# 519_jetson_nano_020002.net
KiCad netlist of a schematic drawn in EAGLE
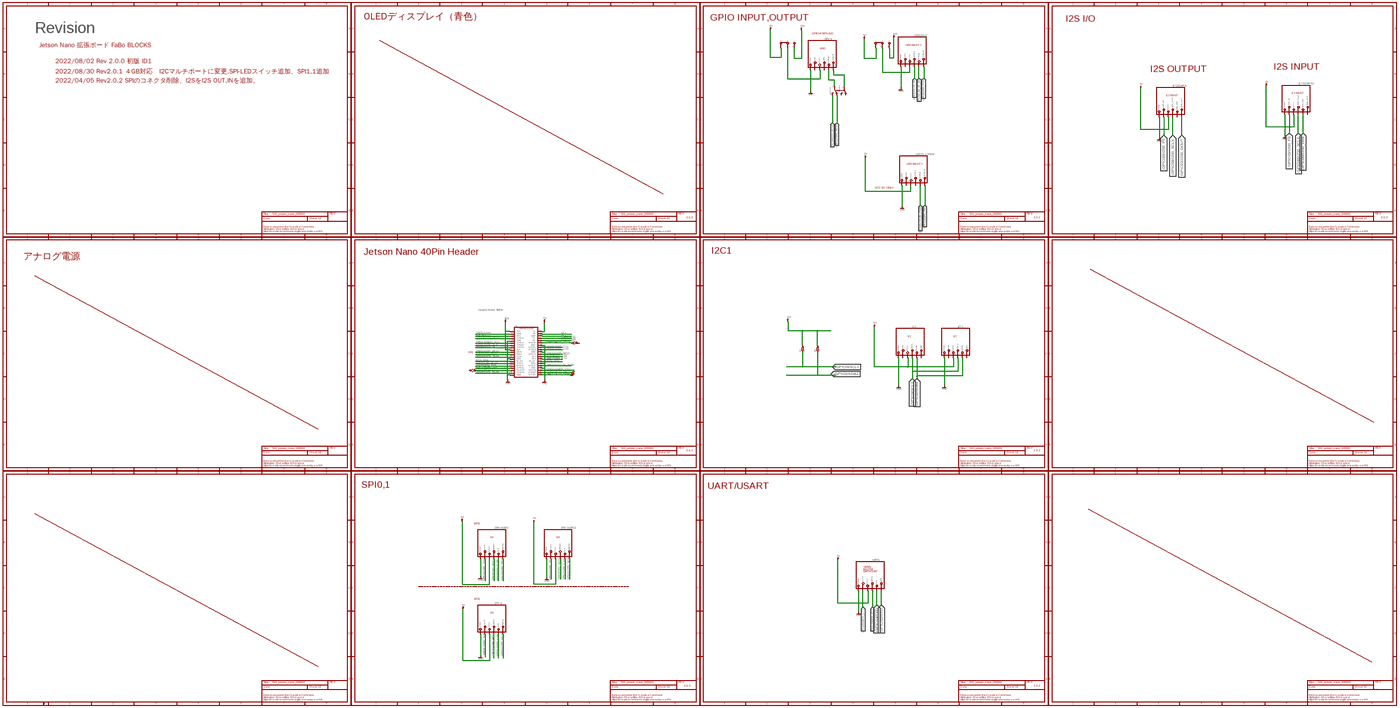
[diagram p0: schematic, sheet 1, overview]
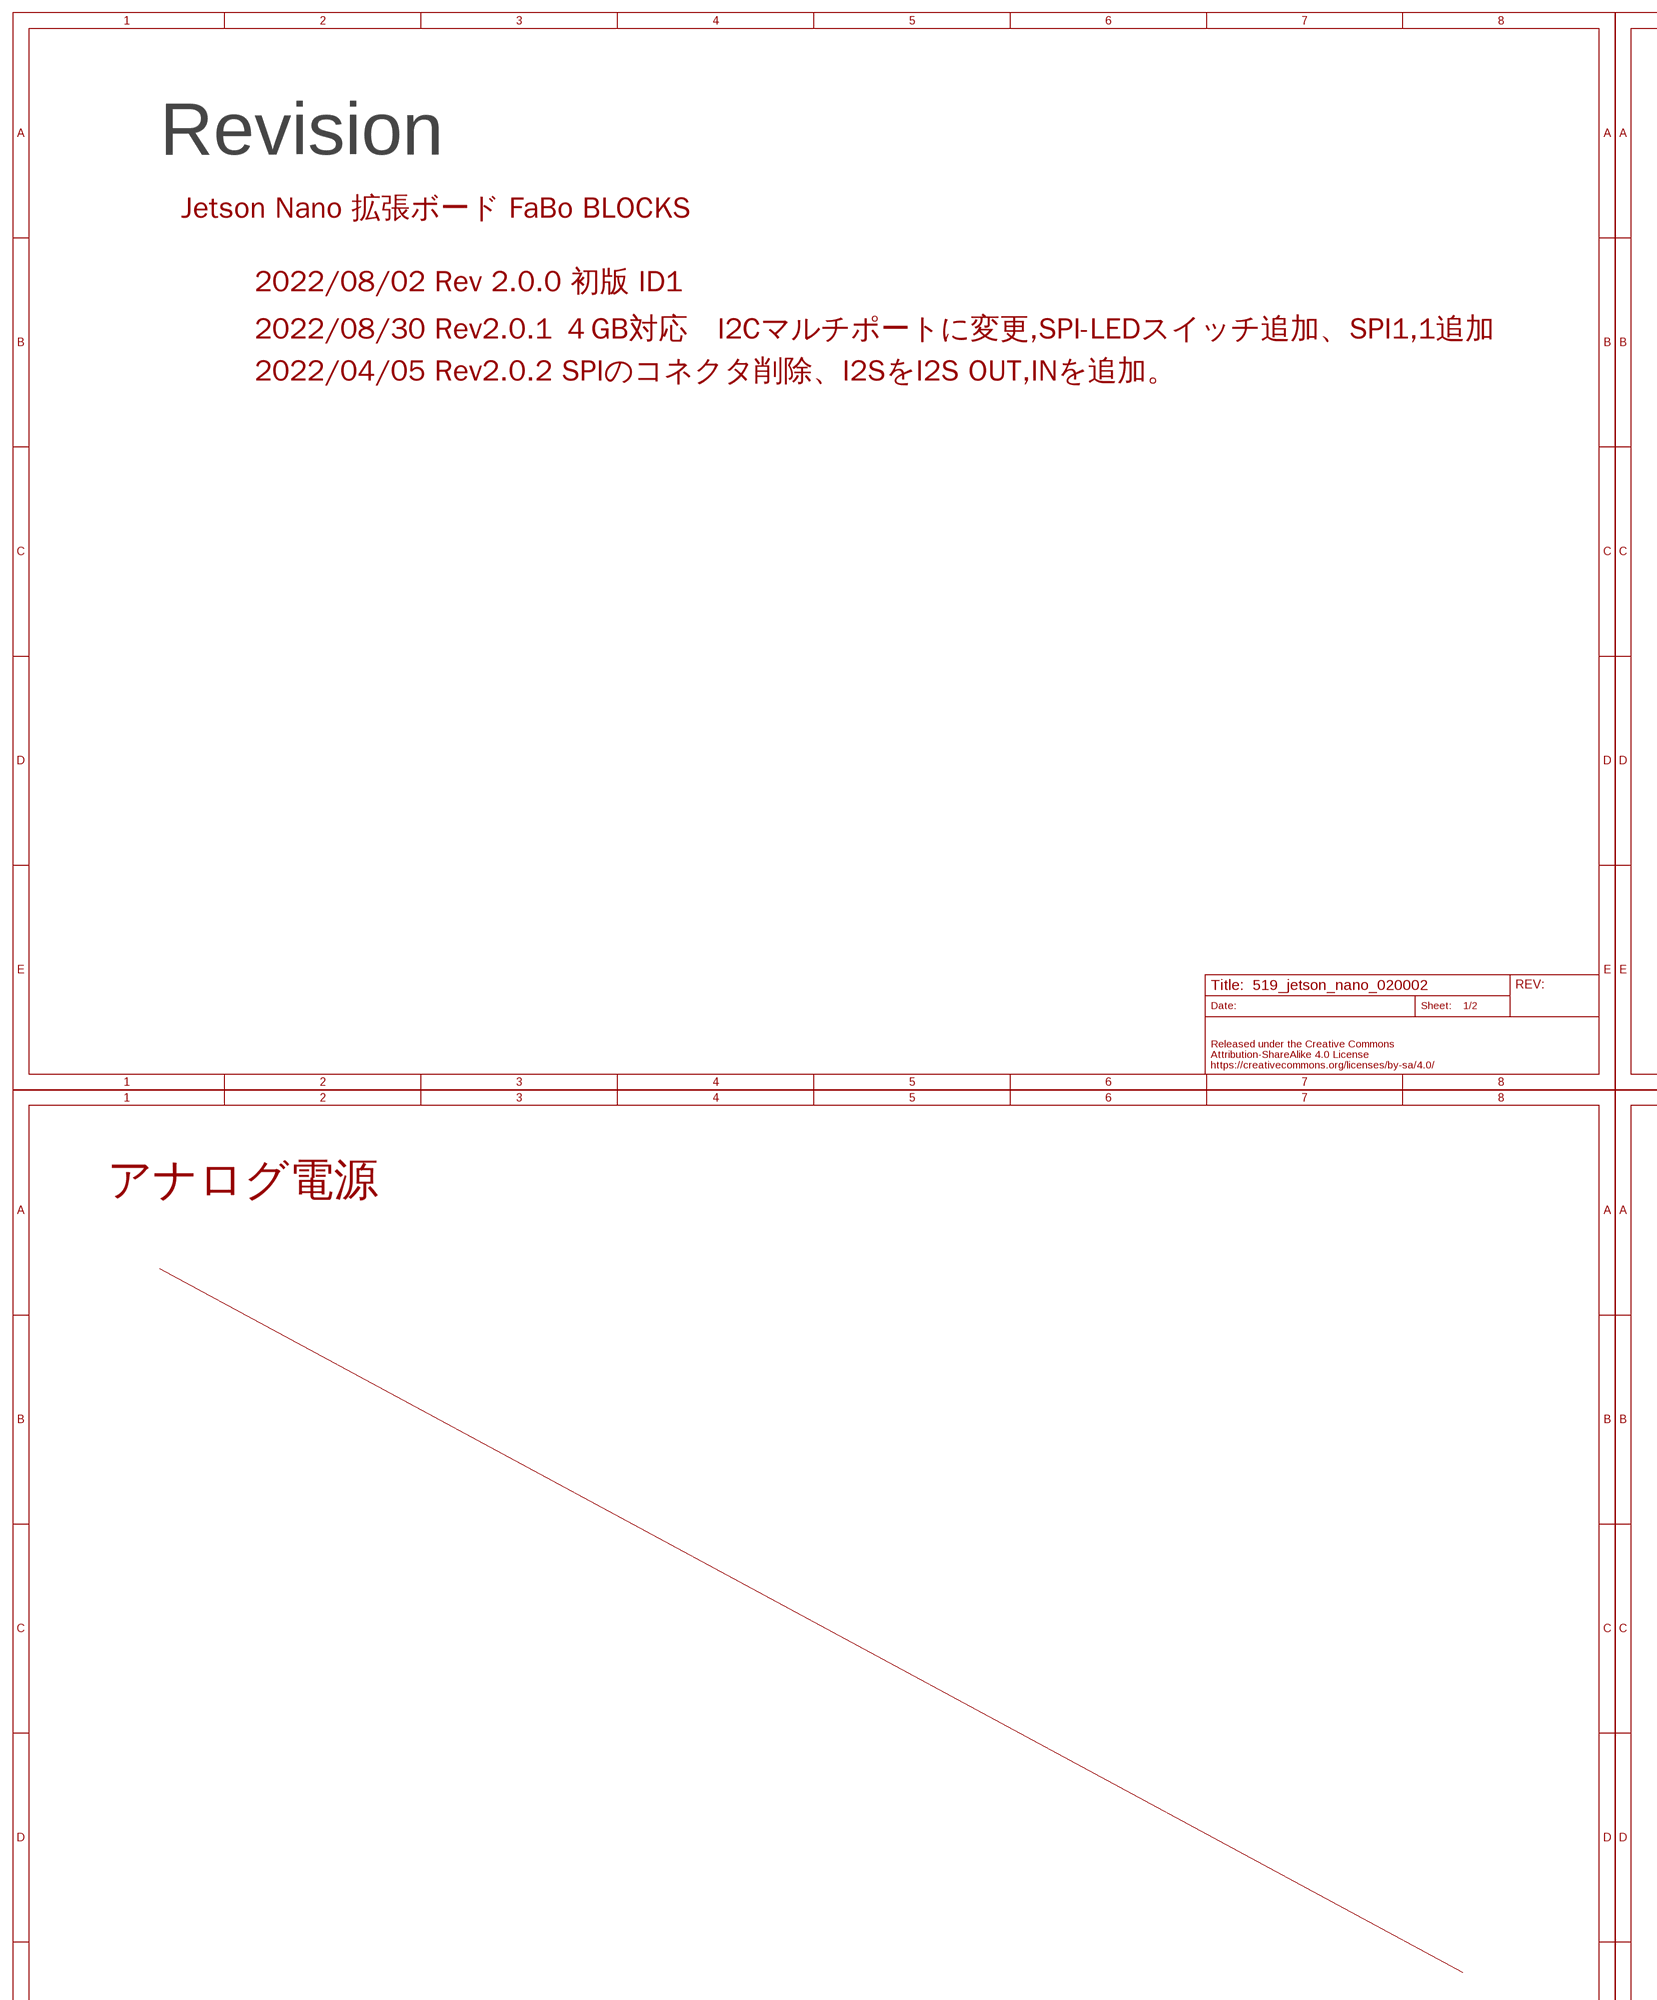
[diagram p1: schematic, sheet 1, part 1 of 8]
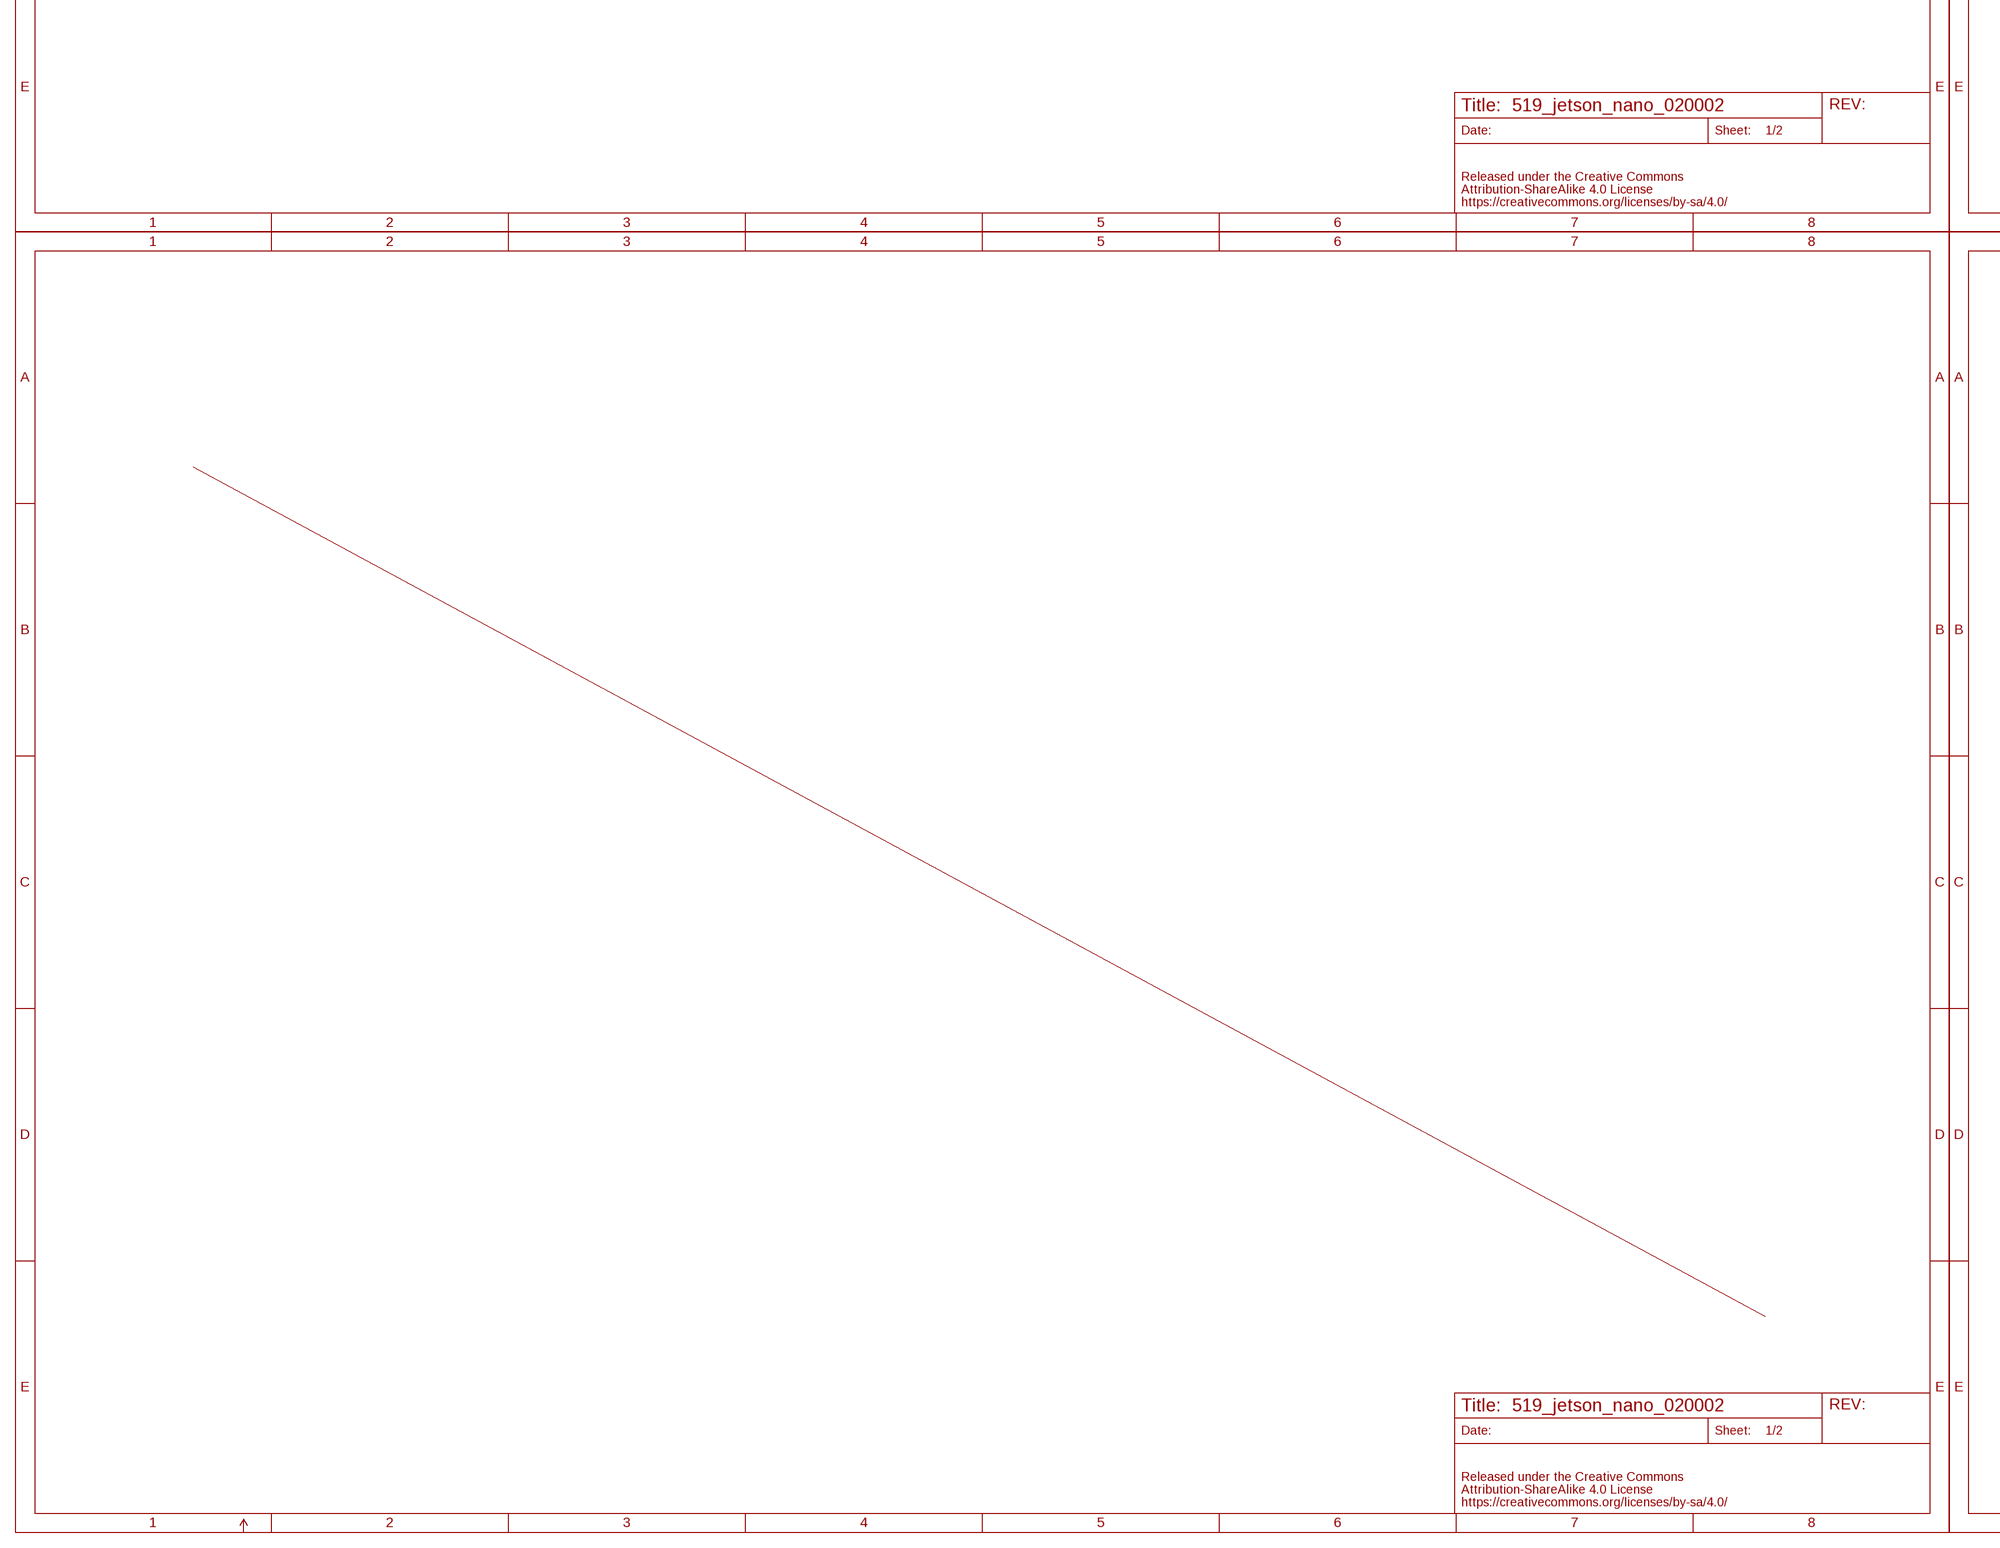
[diagram p2: schematic, sheet 1, part 2 of 8]
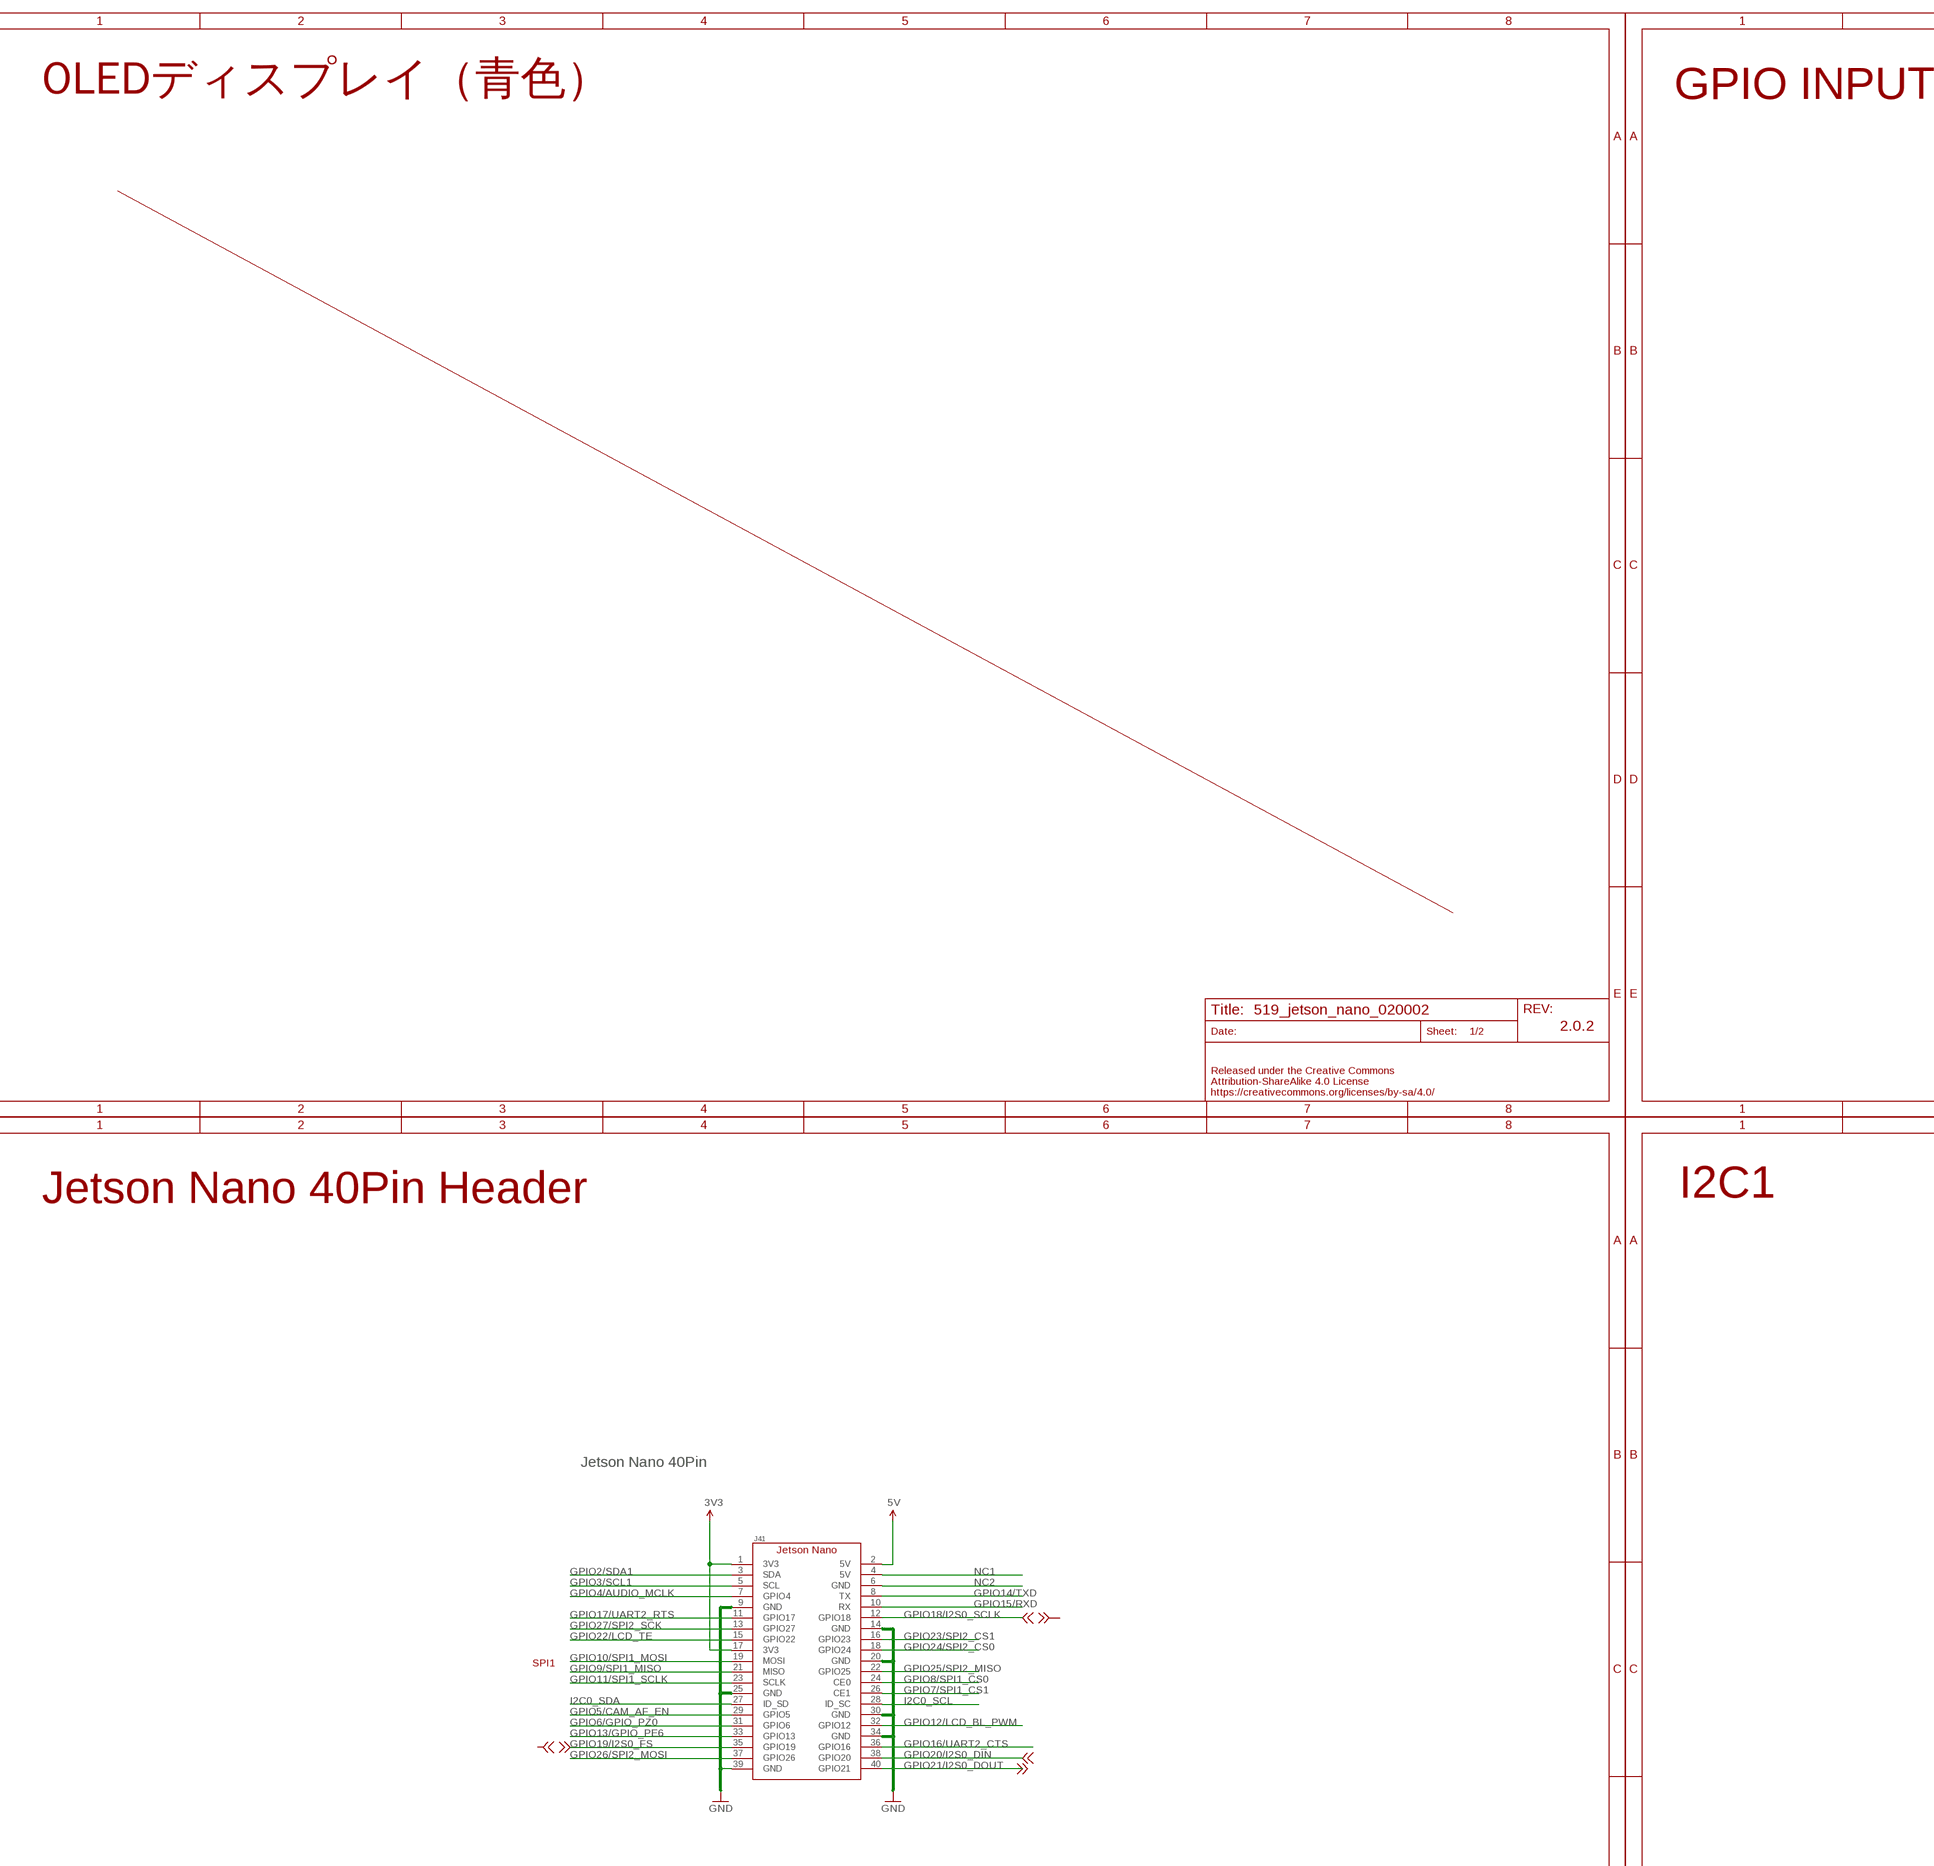
[diagram p3: schematic, sheet 1, part 3 of 8]
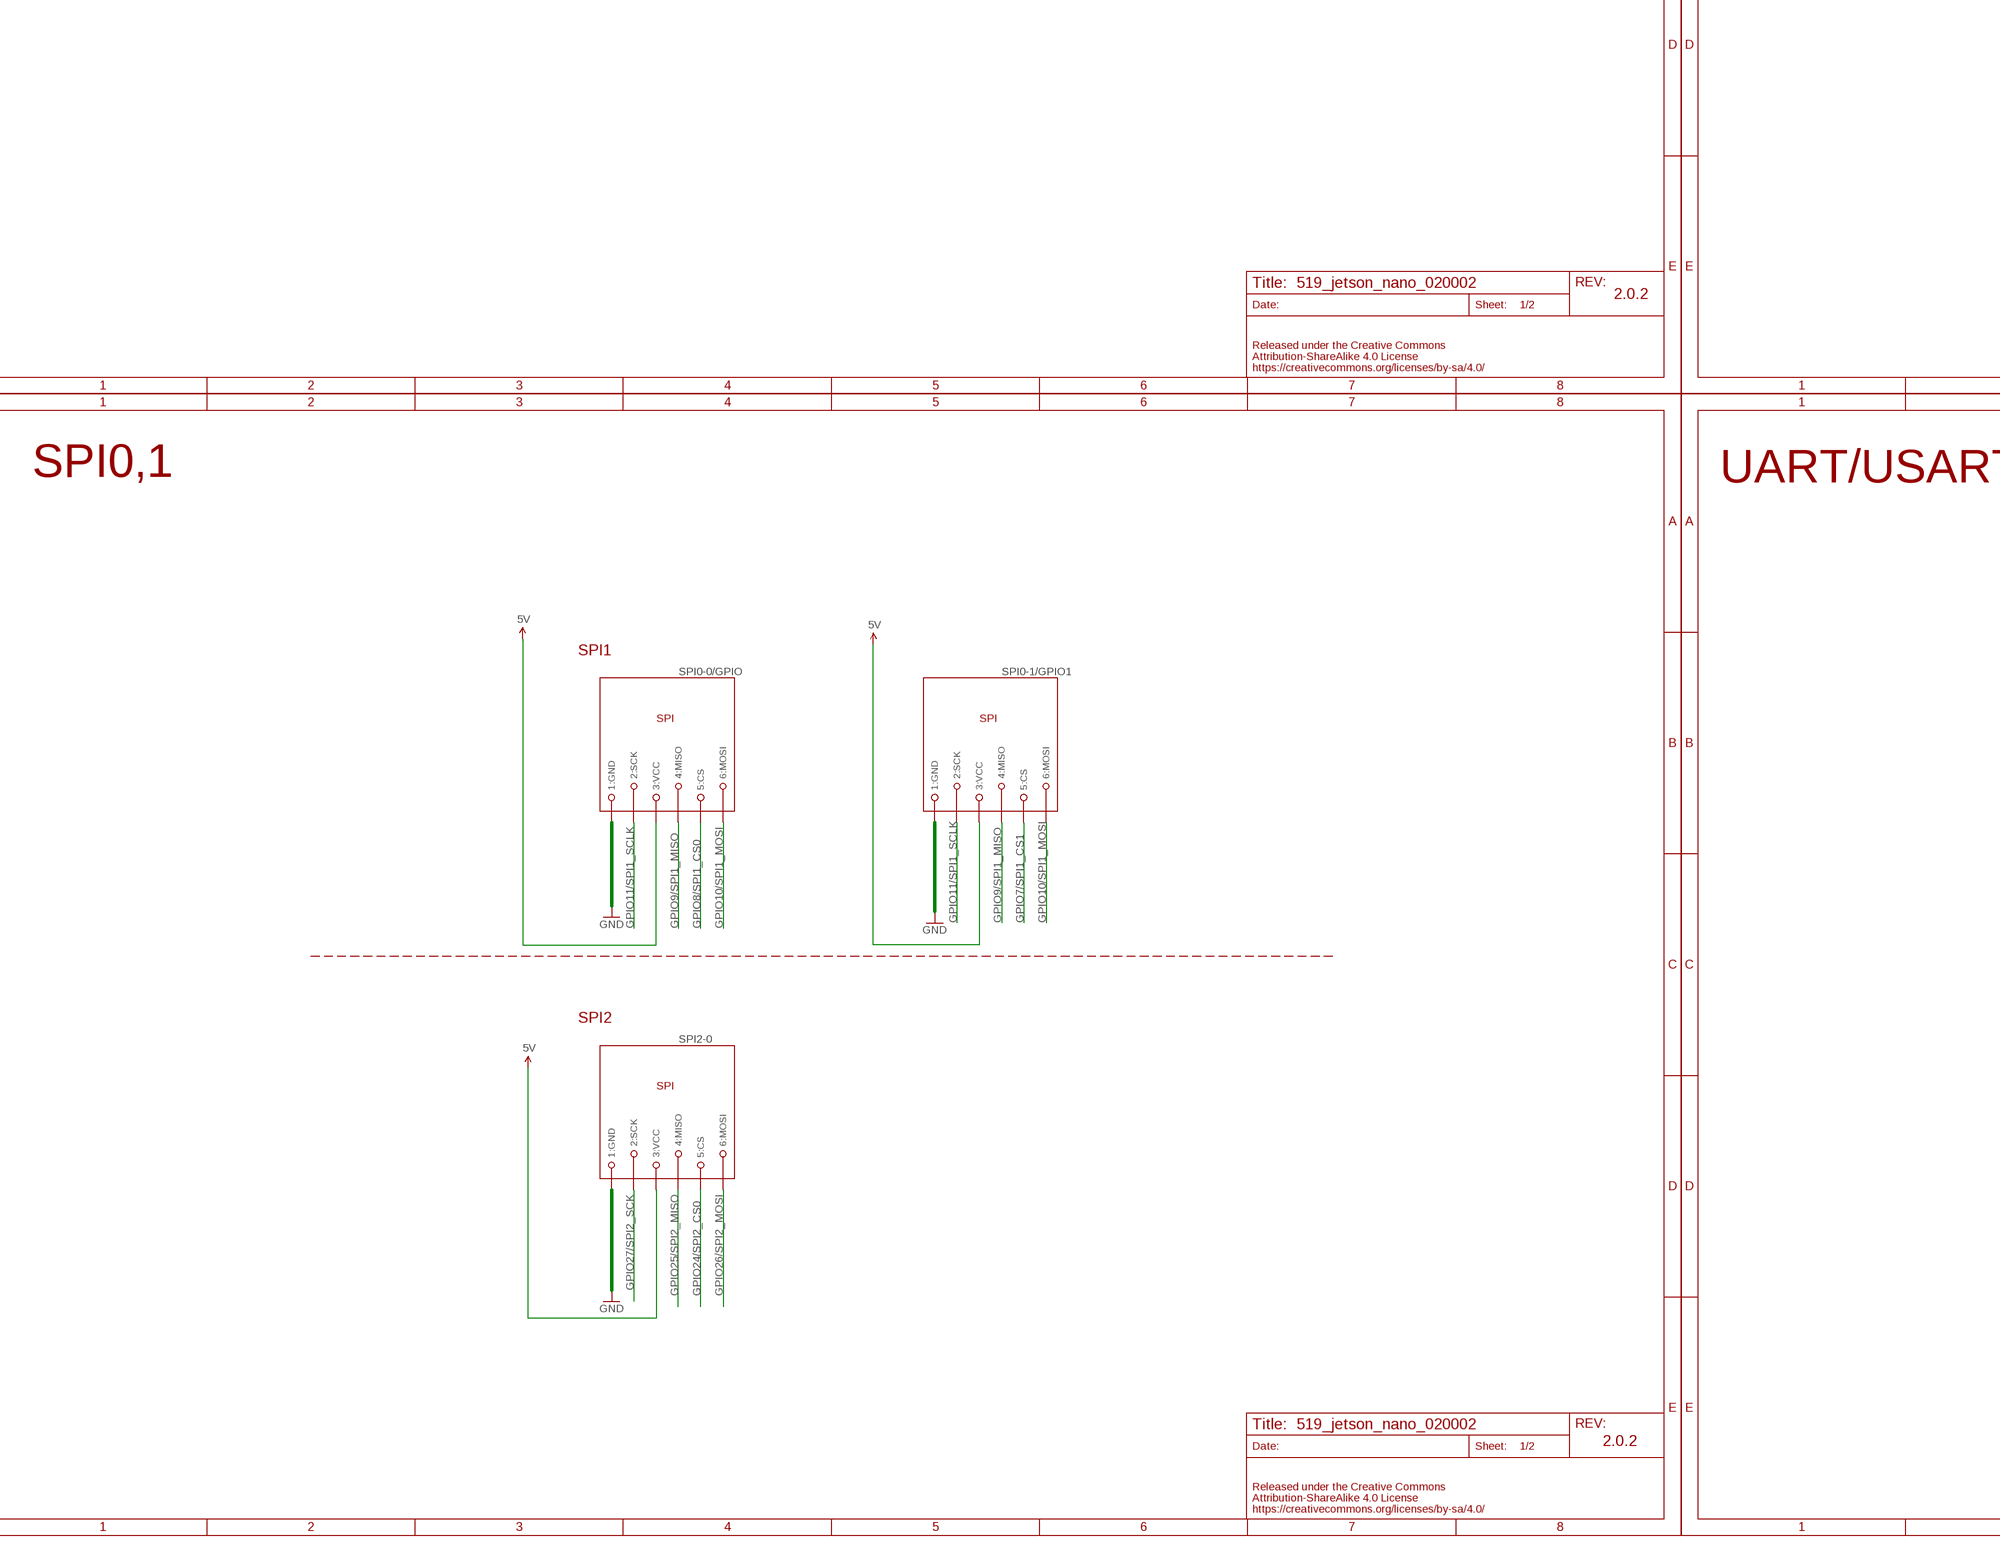
[diagram p4: schematic, sheet 1, part 4 of 8]
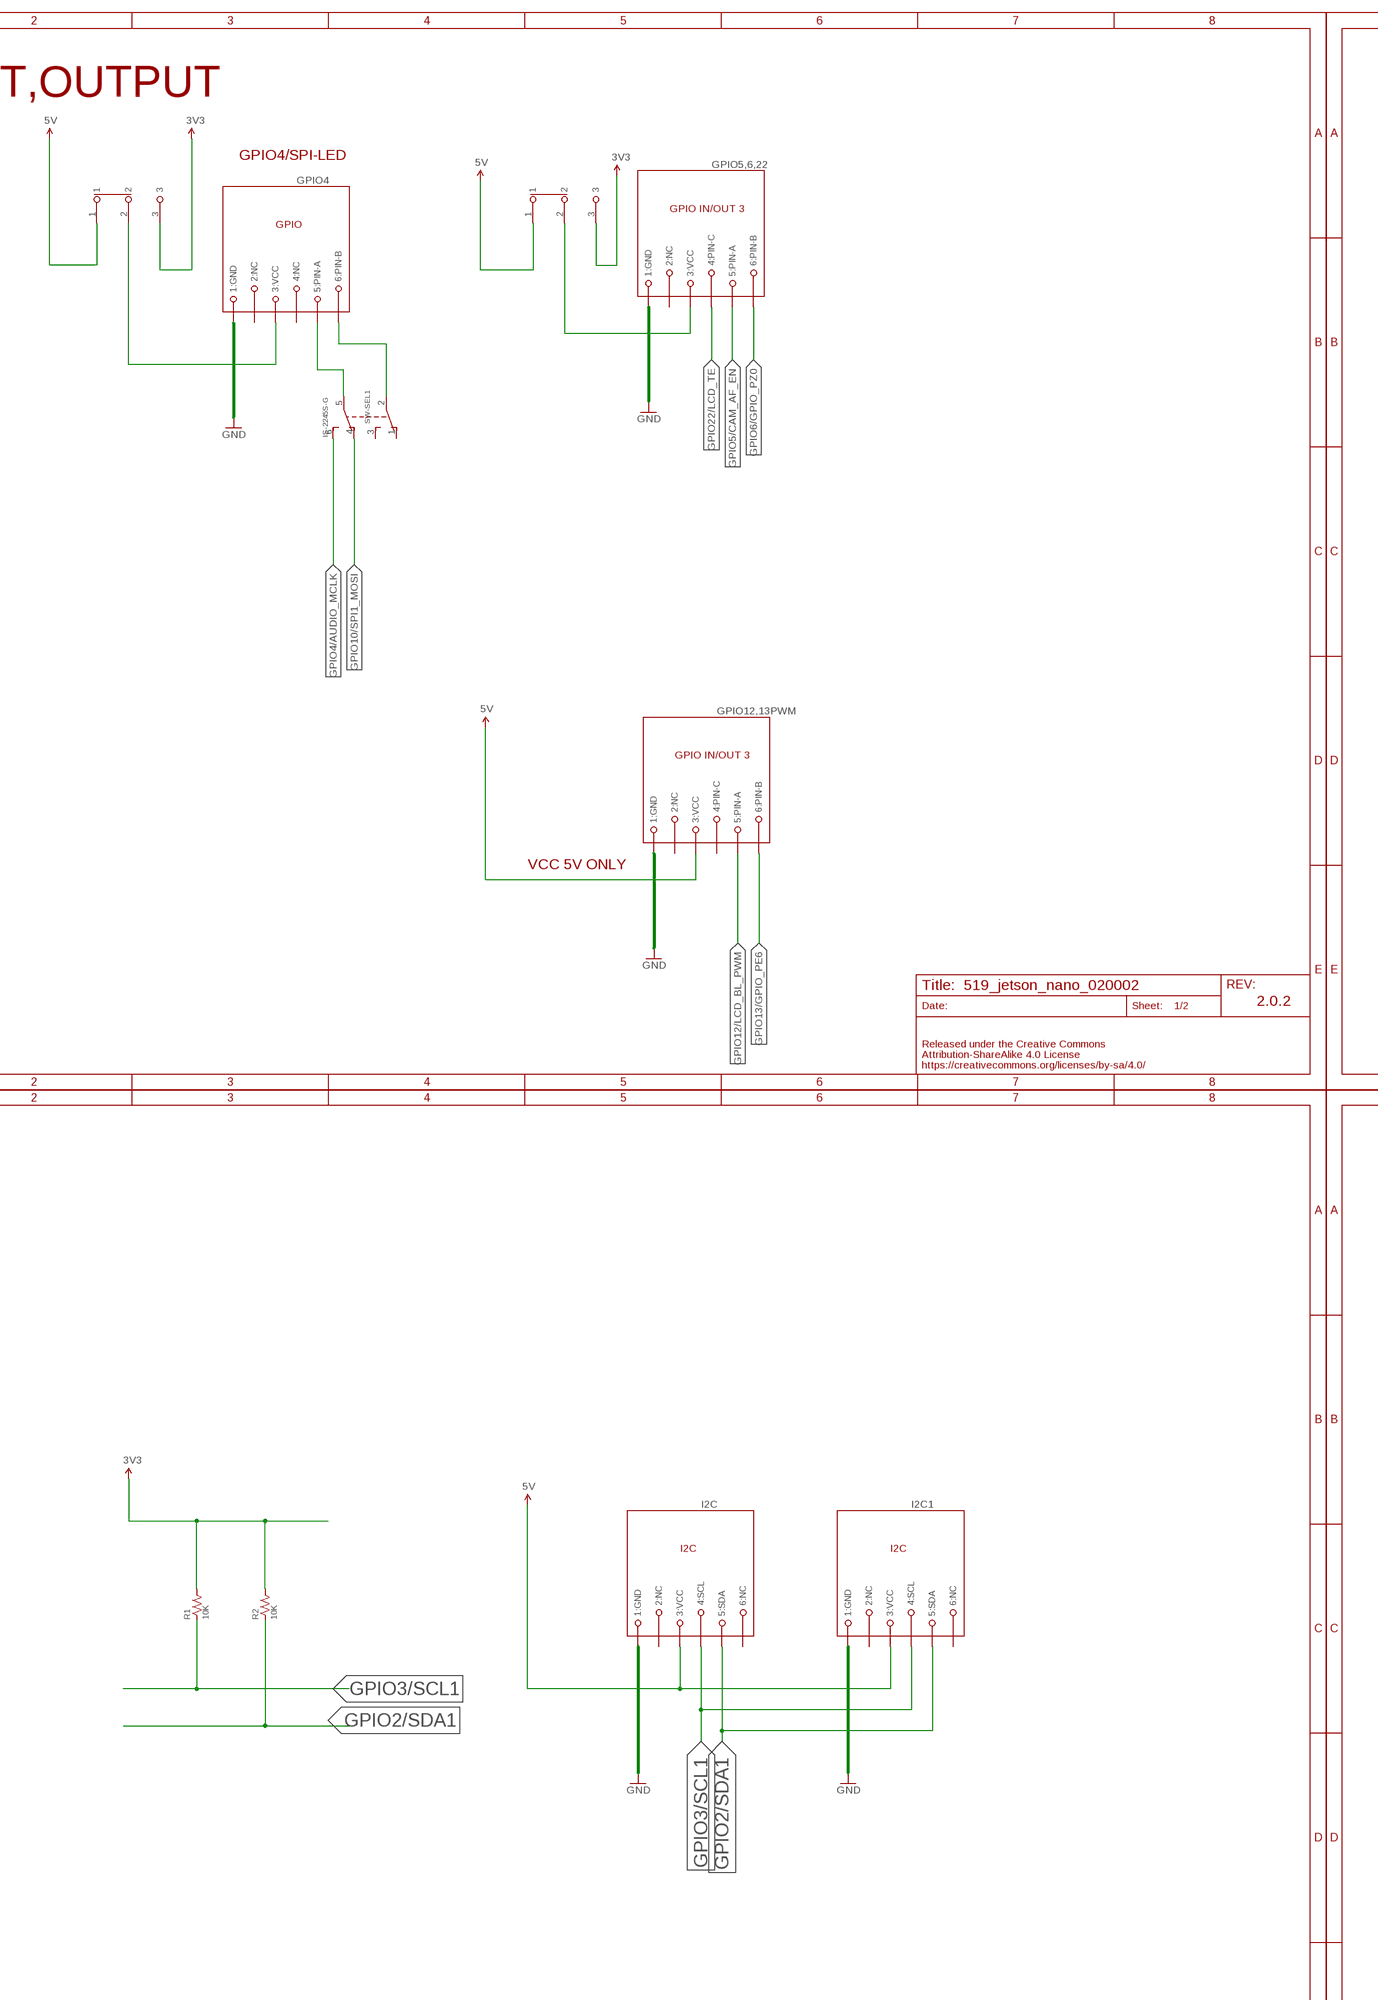
[diagram p5: schematic, sheet 1, part 5 of 8]
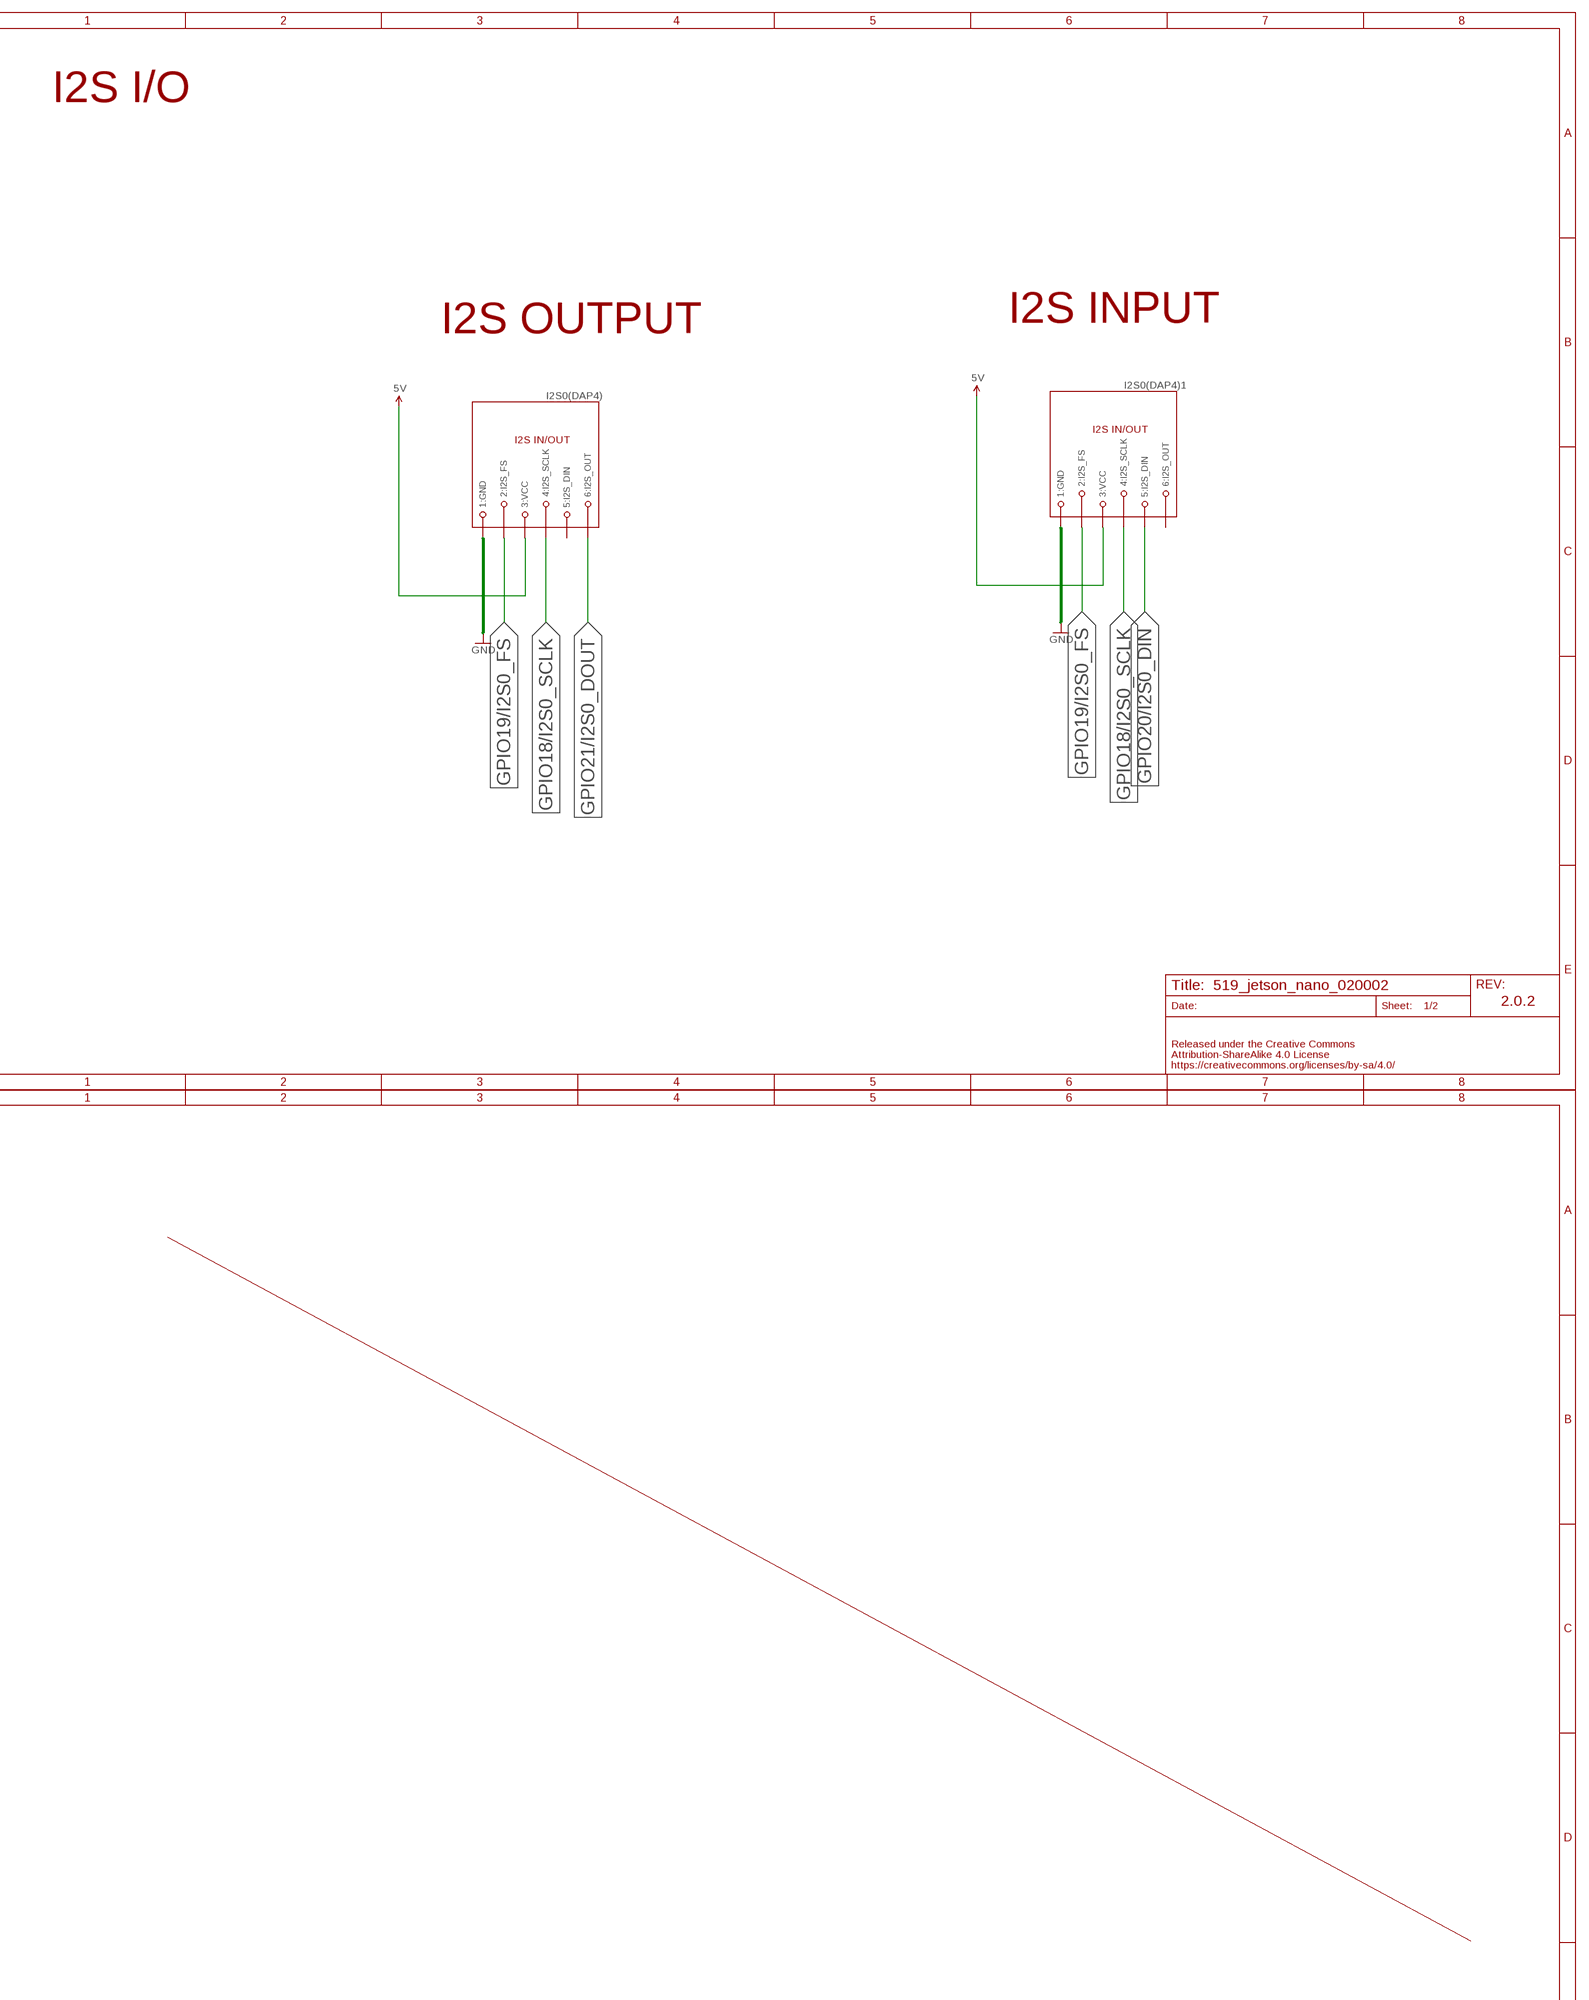
[diagram p6: schematic, sheet 1, part 6 of 8]
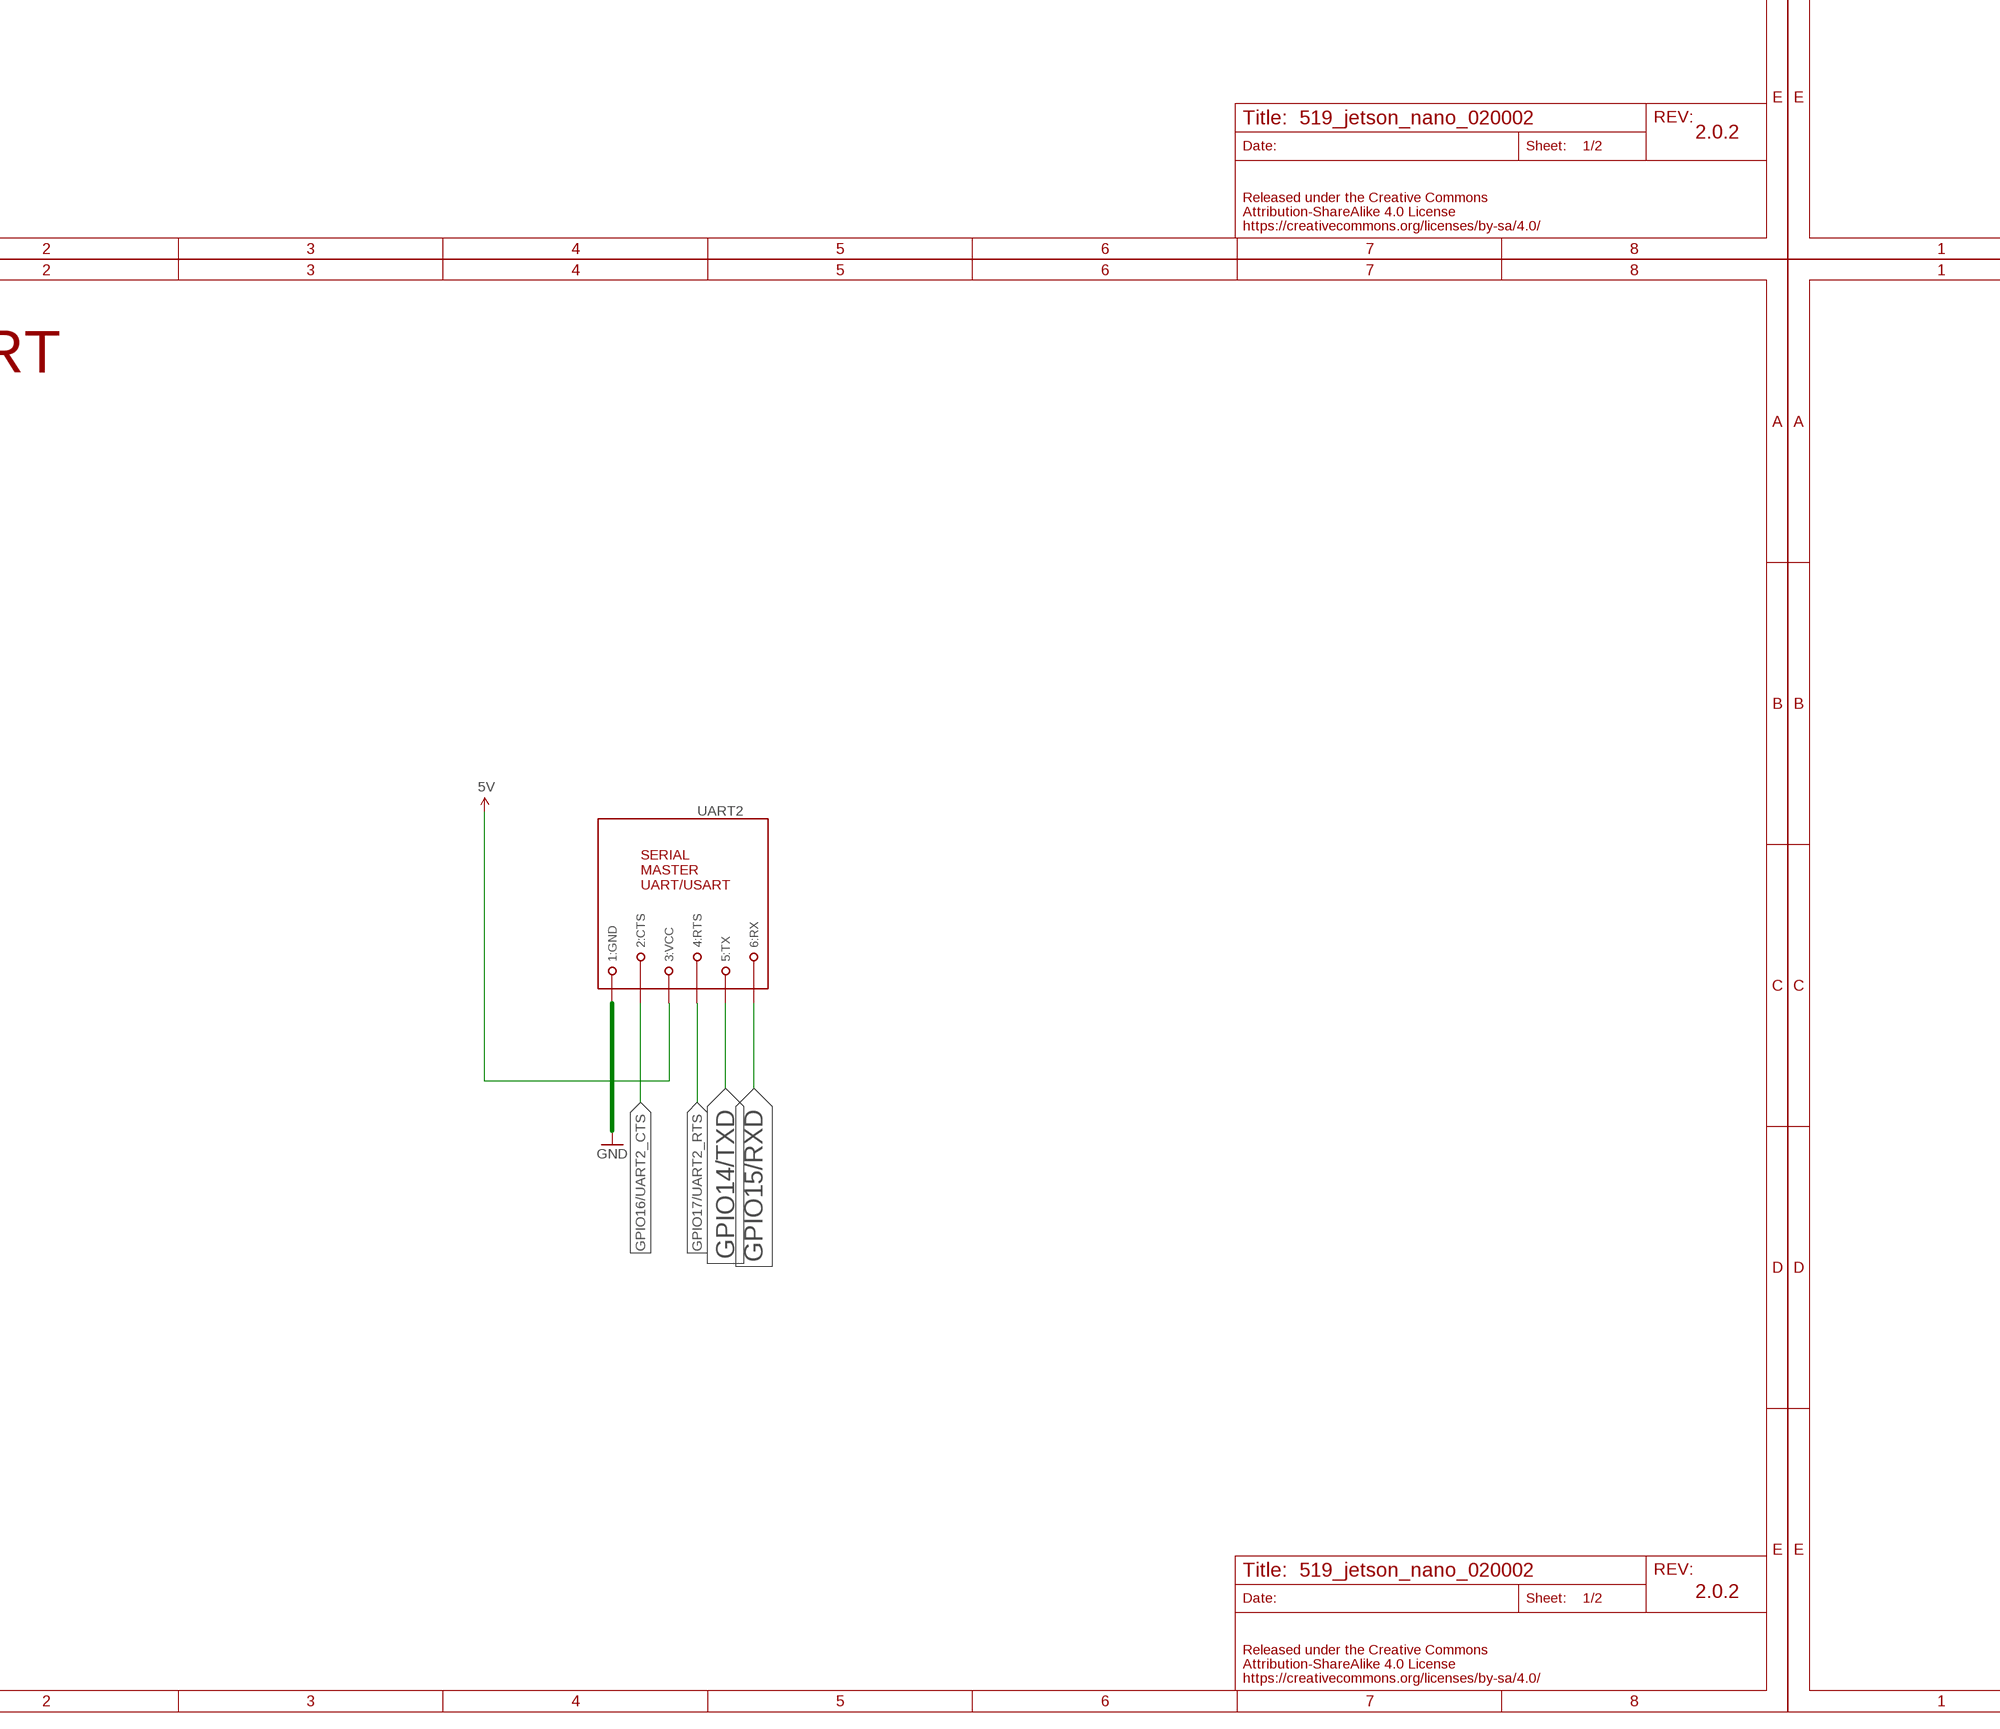
[diagram p7: schematic, sheet 1, part 7 of 8]
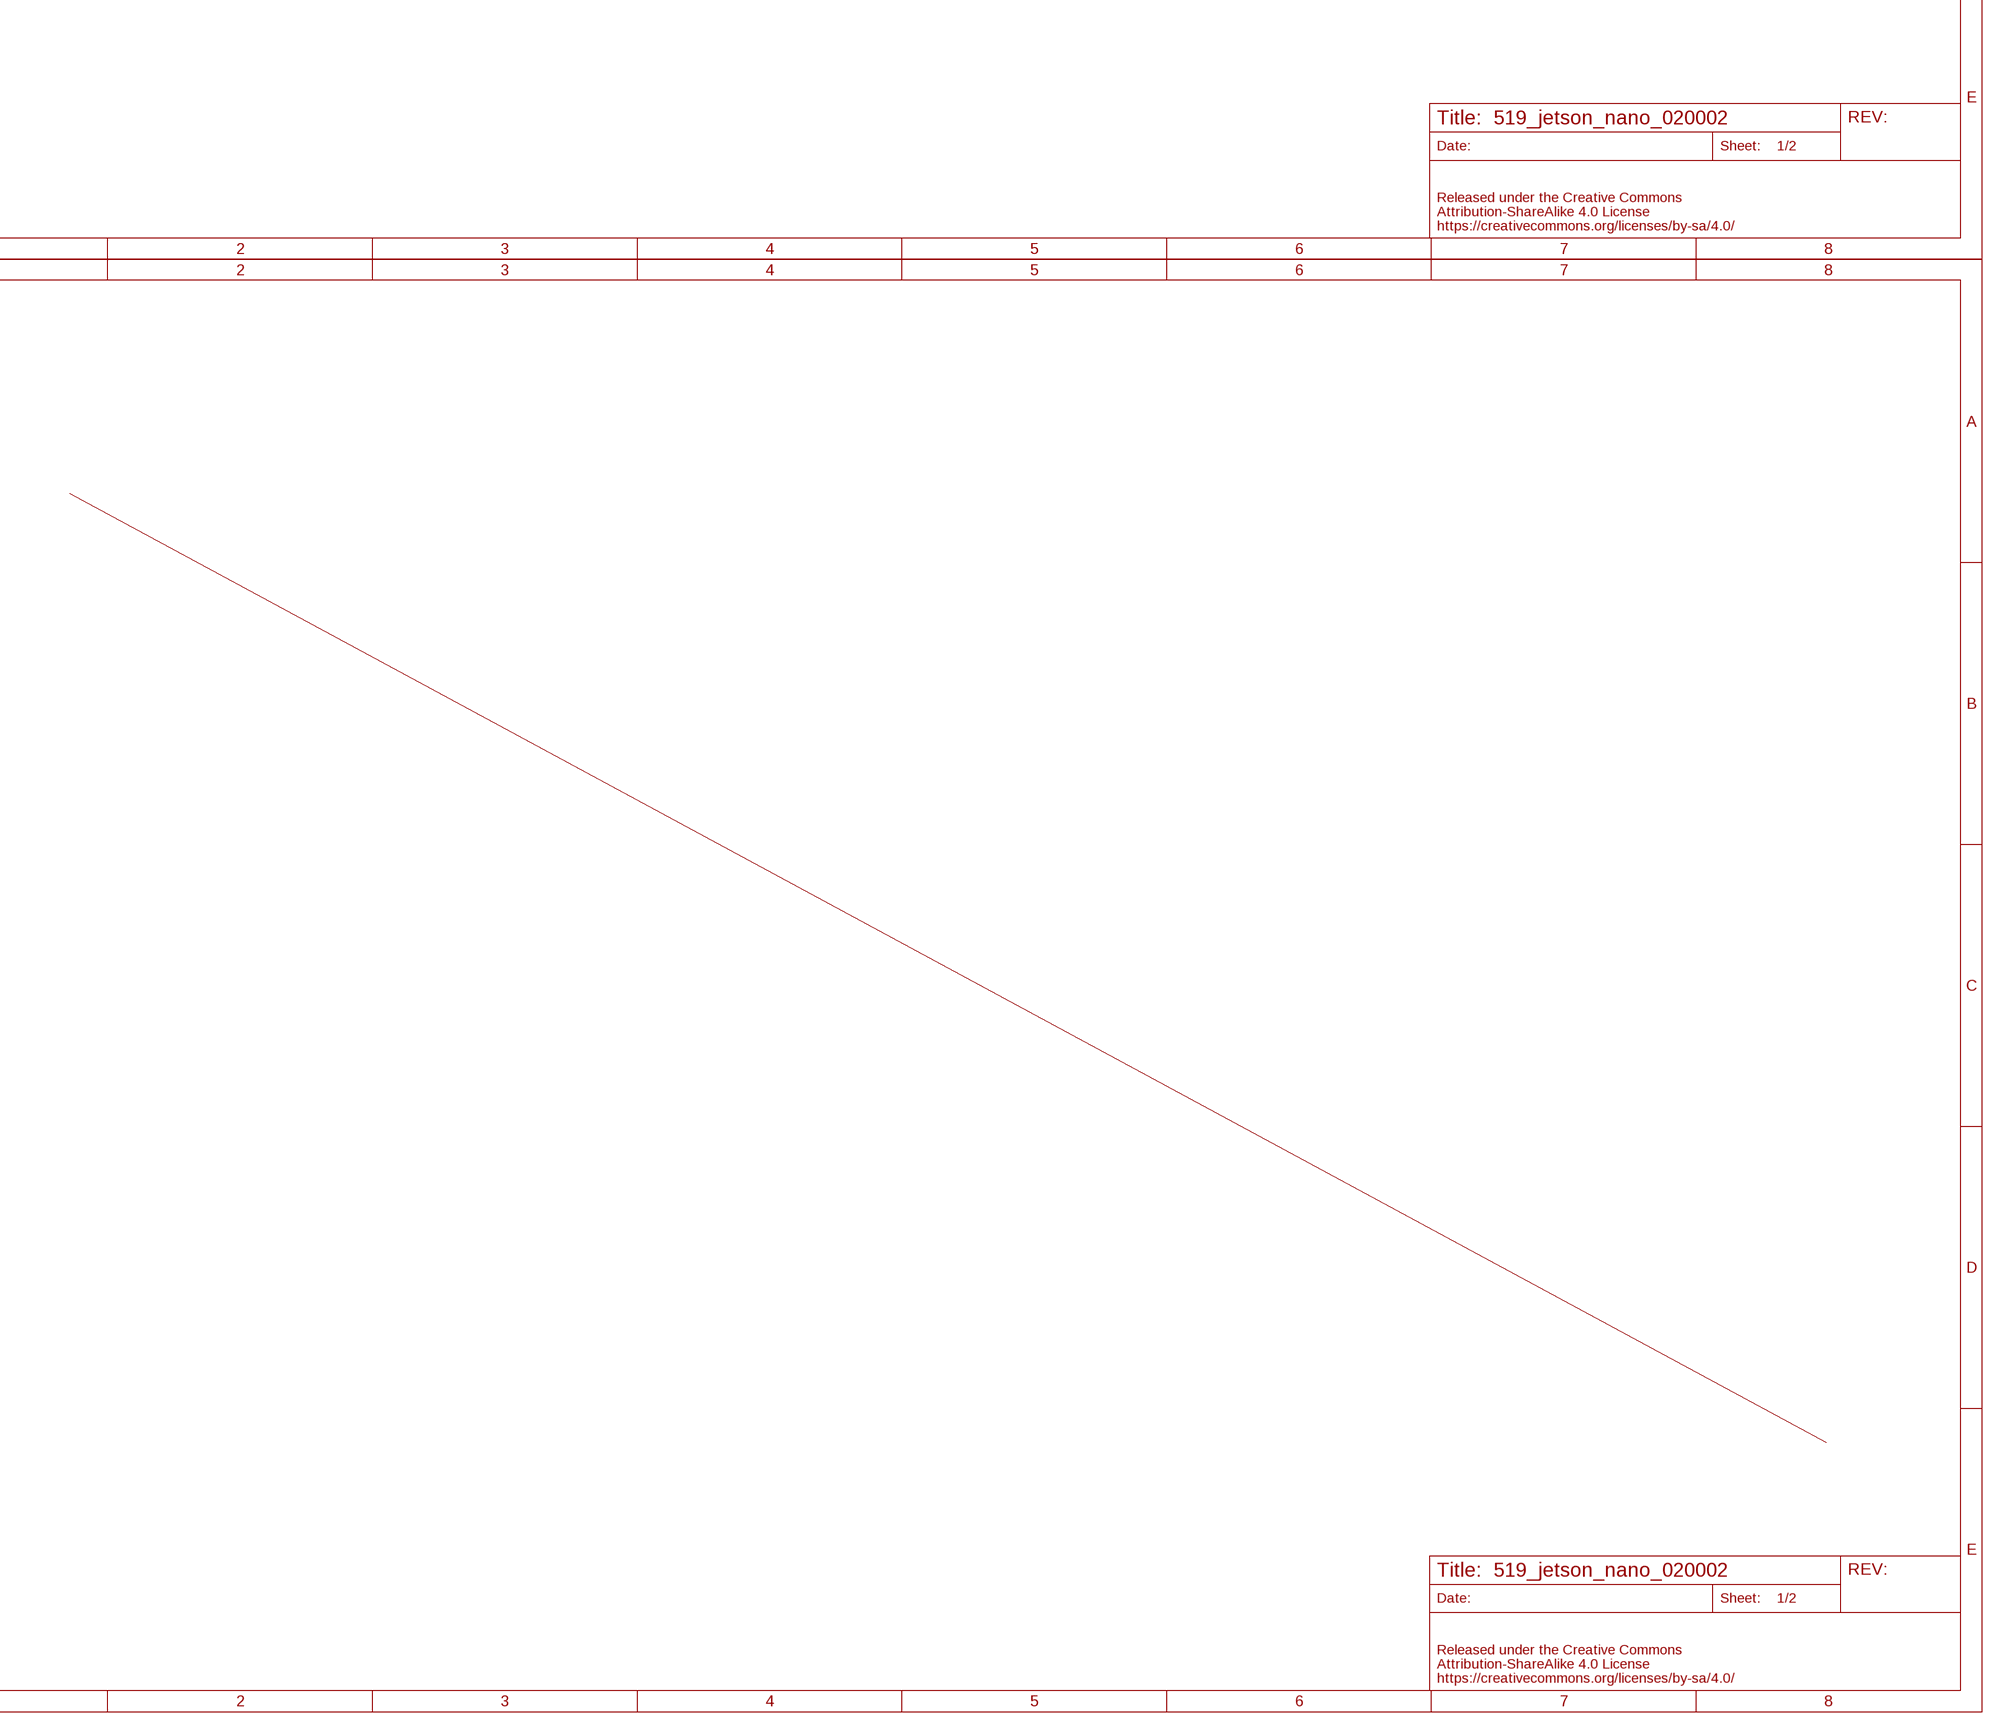
[diagram p8: schematic, sheet 1, part 8 of 8]
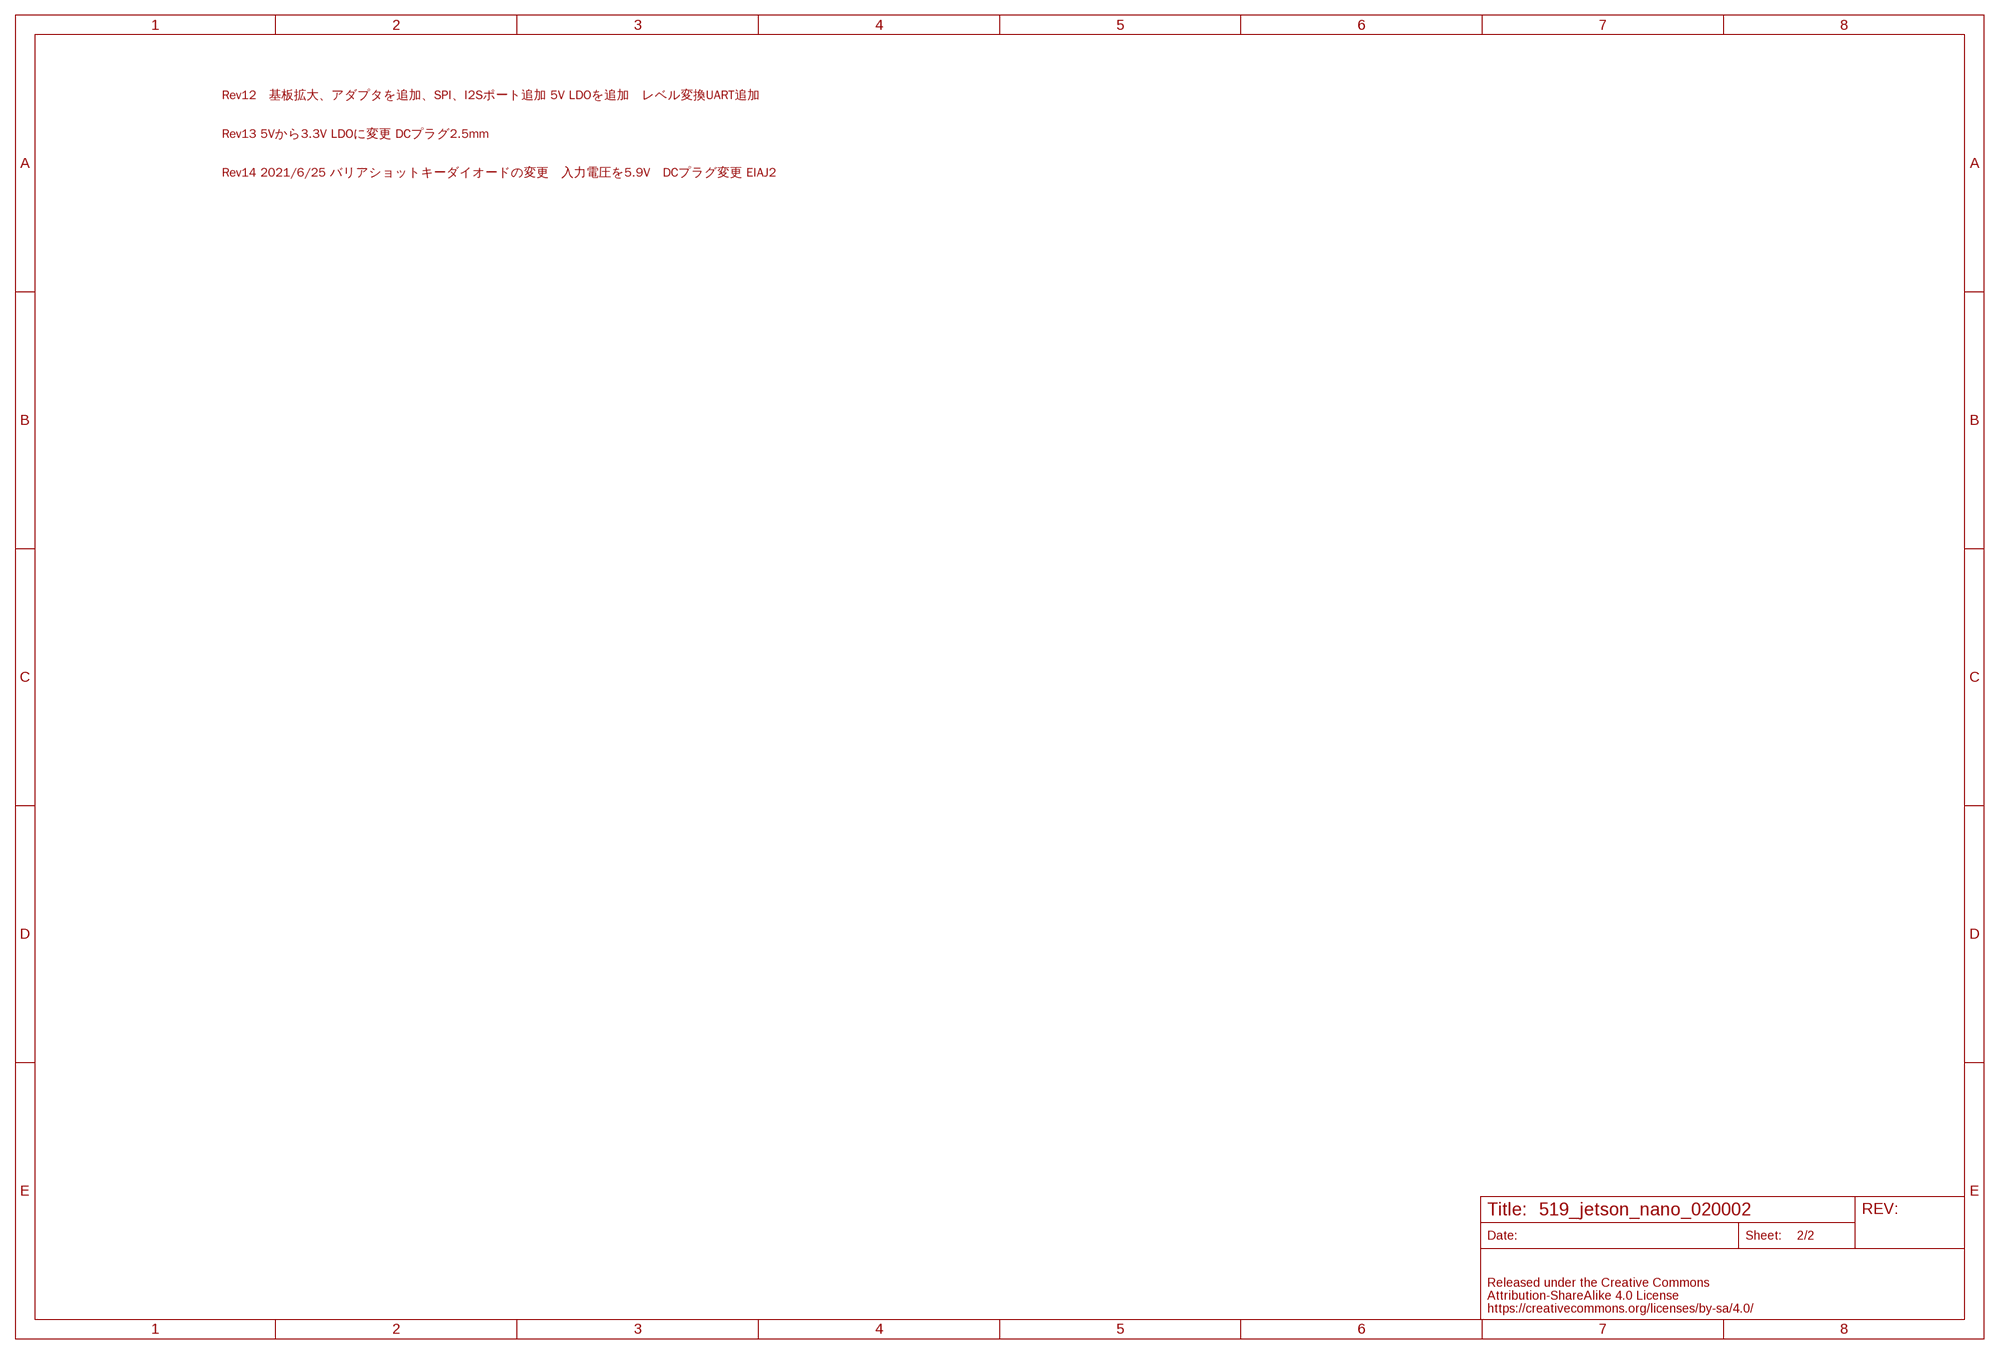
[diagram p9: schematic, sheet 2]

(export (version "E")
  (design (tool "Eeschema 10.0.6"))
  (components
    (comp (ref "GPIO4")
      (value "MODULAR-JACK-6P-RJ11_GPIO")
      (footprint "eagle-import:7002-6PXC-X")
      (libsource (lib "eagle-import") (part "MODULAR-JACK-6P-RJ11_GPIO"))
    )
    (comp (ref "GPIO5,6,22")
      (value "MODULAR-JACK-6P-RJ11_GPIO3")
      (footprint "eagle-import:7002-6PXC-X")
      (libsource (lib "eagle-import") (part "MODULAR-JACK-6P-RJ11_GPIO3"))
    )
    (comp (ref "GPIO12,13PWM")
      (value "MODULAR-JACK-6P-RJ11_GPIO3")
      (footprint "eagle-import:7002-6PXC-X")
      (libsource (lib "eagle-import") (part "MODULAR-JACK-6P-RJ11_GPIO3"))
    )
    (comp (ref "I2C")
      (value "MODULAR-JACK-6P-RJ11_I2C")
      (footprint "eagle-import:7002-6PXC-X")
      (libsource (lib "eagle-import") (part "MODULAR-JACK-6P-RJ11_I2C"))
    )
    (comp (ref "I2C1")
      (value "MODULAR-JACK-6P-RJ11_I2C")
      (footprint "eagle-import:7002-6PXC-X")
      (libsource (lib "eagle-import") (part "MODULAR-JACK-6P-RJ11_I2C"))
    )
    (comp (ref "I2S0(DAP4)")
      (value "MODULAR-JACK-6P-RJ11_I2S_MASTER")
      (footprint "eagle-import:7002-6PXC-X")
      (libsource (lib "eagle-import") (part "MODULAR-JACK-6P-RJ11_I2S_MASTER"))
    )
    (comp (ref "I2S0(DAP4)1")
      (value "MODULAR-JACK-6P-RJ11_I2S_MASTER")
      (footprint "eagle-import:7002-6PXC-X")
      (libsource (lib "eagle-import") (part "MODULAR-JACK-6P-RJ11_I2S_MASTER"))
    )
    (comp (ref "J41")
      (value "JETSON_NANOJETSON_NANO_OVERALL")
      (footprint "eagle-import:JETSON_NANO_DEMENTION")
      (libsource (lib "eagle-import") (part "JETSON_NANOJETSON_NANO_OVERALL"))
    )
    (comp (ref "R1")
      (value "10K")
      (footprint "eagle-import:0402")
      (libsource (lib "eagle-import") (part "RESISTOR-0402"))
    )
    (comp (ref "R2")
      (value "10K")
      (footprint "eagle-import:0402")
      (libsource (lib "eagle-import") (part "RESISTOR-0402"))
    )
    (comp (ref "SPI0-0/GPIO")
      (value "MODULAR-JACK-6P-RJ11_SPI")
      (footprint "eagle-import:7002-6PXC-X")
      (libsource (lib "eagle-import") (part "MODULAR-JACK-6P-RJ11_SPI"))
    )
    (comp (ref "SPI0-1/GPIO1")
      (value "MODULAR-JACK-6P-RJ11_SPI")
      (footprint "eagle-import:7002-6PXC-X")
      (libsource (lib "eagle-import") (part "MODULAR-JACK-6P-RJ11_SPI"))
    )
    (comp (ref "SPI2-0")
      (value "MODULAR-JACK-6P-RJ11_SPI")
      (footprint "eagle-import:7002-6PXC-X")
      (libsource (lib "eagle-import") (part "MODULAR-JACK-6P-RJ11_SPI"))
    )
    (comp (ref "SW-SEL1")
      (value "IS-2245S-G")
      (footprint "eagle-import:IS-2245S-G")
      (libsource (lib "eagle-import") (part "IS-2245S-G"))
    )
    (comp (ref "U$3")
      (value "SSSS213202")
      (footprint "eagle-import:SSSS213202")
      (libsource (lib "eagle-import") (part "SSSS213202"))
    )
    (comp (ref "U$32")
      (value "SSSS213202")
      (footprint "eagle-import:SSSS213202")
      (libsource (lib "eagle-import") (part "SSSS213202"))
    )
    (comp (ref "UART2")
      (value "MODULAR-JACK-6P-RJ11_SERIAL_M_USART")
      (footprint "eagle-import:7002-6PXC-X")
      (libsource (lib "eagle-import") (part "MODULAR-JACK-6P-RJ11_SERIAL_M_USART"))
    )
  )
  (nets
    (net (code "1") (name "3V3") (class "Default")
      (node (ref "J41") (pin "1") (pinfunction "3V3_1") (pintype "bidirectional"))
      (node (ref "J41") (pin "17") (pinfunction "3V3_17") (pintype "bidirectional"))
      (node (ref "R1") (pin "2") (pinfunction "2_2") (pintype "bidirectional"))
      (node (ref "R2") (pin "2") (pinfunction "2_2") (pintype "bidirectional"))
      (node (ref "U$3") (pin "3") (pinfunction "3_3") (pintype "bidirectional"))
      (node (ref "U$32") (pin "3") (pinfunction "3_3") (pintype "bidirectional"))
    )
    (net (code "2") (name "5V") (class "Default")
      (node (ref "GPIO12,13PWM") (pin "3") (pinfunction "3:VCC_3") (pintype "power_in"))
      (node (ref "I2C") (pin "3") (pinfunction "3:VCC_3") (pintype "power_in"))
      (node (ref "I2C1") (pin "3") (pinfunction "3:VCC_3") (pintype "power_in"))
      (node (ref "I2S0(DAP4)") (pin "3") (pinfunction "3:VCC_3") (pintype "power_in"))
      (node (ref "I2S0(DAP4)1") (pin "3") (pinfunction "3:VCC_3") (pintype "power_in"))
      (node (ref "J41") (pin "2") (pinfunction "5V_2") (pintype "bidirectional"))
      (node (ref "SPI0-0/GPIO") (pin "3") (pinfunction "3:VCC_3") (pintype "power_in"))
      (node (ref "SPI0-1/GPIO1") (pin "3") (pinfunction "3:VCC_3") (pintype "power_in"))
      (node (ref "SPI2-0") (pin "3") (pinfunction "3:VCC_3") (pintype "power_in"))
      (node (ref "U$3") (pin "1") (pinfunction "1_1") (pintype "bidirectional"))
      (node (ref "U$32") (pin "1") (pinfunction "1_1") (pintype "bidirectional"))
      (node (ref "UART2") (pin "3") (pinfunction "3:VCC_3") (pintype "power_in"))
    )
    (net (code "3") (name "GND") (class "Default")
      (node (ref "GPIO12,13PWM") (pin "1") (pinfunction "1:GND_1") (pintype "power_in"))
      (node (ref "GPIO4") (pin "1") (pinfunction "1:GND_1") (pintype "power_in"))
      (node (ref "GPIO5,6,22") (pin "1") (pinfunction "1:GND_1") (pintype "power_in"))
      (node (ref "I2C") (pin "1") (pinfunction "1:GND_1") (pintype "power_in"))
      (node (ref "I2C1") (pin "1") (pinfunction "1:GND_1") (pintype "power_in"))
      (node (ref "I2S0(DAP4)") (pin "1") (pinfunction "1:GND_1") (pintype "power_in"))
      (node (ref "I2S0(DAP4)1") (pin "1") (pinfunction "1:GND_1") (pintype "power_in"))
      (node (ref "J41") (pin "14") (pinfunction "GND_14") (pintype "bidirectional"))
      (node (ref "J41") (pin "20") (pinfunction "GND_20") (pintype "bidirectional"))
      (node (ref "J41") (pin "25") (pinfunction "GND_25") (pintype "bidirectional"))
      (node (ref "J41") (pin "30") (pinfunction "GND_30") (pintype "bidirectional"))
      (node (ref "J41") (pin "34") (pinfunction "GND_34") (pintype "bidirectional"))
      (node (ref "J41") (pin "39") (pinfunction "GND_39") (pintype "bidirectional"))
      (node (ref "J41") (pin "9") (pinfunction "GND_9") (pintype "bidirectional"))
      (node (ref "SPI0-0/GPIO") (pin "1") (pinfunction "1:GND_1") (pintype "power_in"))
      (node (ref "SPI0-1/GPIO1") (pin "1") (pinfunction "1:GND_1") (pintype "power_in"))
      (node (ref "SPI2-0") (pin "1") (pinfunction "1:GND_1") (pintype "power_in"))
      (node (ref "UART2") (pin "1") (pinfunction "1:GND_1") (pintype "power_in"))
    )
    (net (code "4") (name "GPIO2{slash}SDA1") (class "Default")
      (node (ref "I2C") (pin "5") (pinfunction "5:SDA_5") (pintype "open_collector"))
      (node (ref "I2C1") (pin "5") (pinfunction "5:SDA_5") (pintype "open_collector"))
      (node (ref "J41") (pin "3") (pinfunction "SDA_3") (pintype "bidirectional"))
      (node (ref "R2") (pin "1") (pinfunction "1_1") (pintype "bidirectional"))
    )
    (net (code "5") (name "GPIO3{slash}SCL1") (class "Default")
      (node (ref "I2C") (pin "4") (pinfunction "4:SCL_4") (pintype "open_collector"))
      (node (ref "I2C1") (pin "4") (pinfunction "4:SCL_4") (pintype "open_collector"))
      (node (ref "J41") (pin "5") (pinfunction "SCL_5") (pintype "bidirectional"))
      (node (ref "R1") (pin "1") (pinfunction "1_1") (pintype "bidirectional"))
    )
    (net (code "6") (name "GPIO4{slash}AUDIO_MCLK") (class "Default")
      (node (ref "J41") (pin "7") (pinfunction "GPIO4_7") (pintype "bidirectional"))
      (node (ref "SW-SEL1") (pin "6") (pinfunction "6_6") (pintype "passive"))
    )
    (net (code "7") (name "GPIO5{slash}CAM_AF_EN") (class "Default")
      (node (ref "GPIO5,6,22") (pin "5") (pinfunction "5:PIN-A_5") (pintype "bidirectional"))
      (node (ref "J41") (pin "29") (pinfunction "GPIO5_29") (pintype "bidirectional"))
    )
    (net (code "8") (name "GPIO6{slash}GPIO_PZ0") (class "Default")
      (node (ref "GPIO5,6,22") (pin "6") (pinfunction "6:PIN-B_6") (pintype "bidirectional"))
      (node (ref "J41") (pin "31") (pinfunction "GPIO6_31") (pintype "bidirectional"))
    )
    (net (code "9") (name "GPIO7{slash}SPI1_CS1") (class "Default")
      (node (ref "J41") (pin "26") (pinfunction "CE1_26") (pintype "bidirectional"))
      (node (ref "SPI0-1/GPIO1") (pin "5") (pinfunction "5:CS_5") (pintype "open_collector"))
    )
    (net (code "10") (name "GPIO8{slash}SPI1_CS0") (class "Default")
      (node (ref "J41") (pin "24") (pinfunction "CE0_24") (pintype "bidirectional"))
      (node (ref "SPI0-0/GPIO") (pin "5") (pinfunction "5:CS_5") (pintype "open_collector"))
    )
    (net (code "11") (name "GPIO9{slash}SPI1_MISO") (class "Default")
      (node (ref "J41") (pin "21") (pinfunction "MISO_21") (pintype "bidirectional"))
      (node (ref "SPI0-0/GPIO") (pin "4") (pinfunction "4:MISO_4") (pintype "open_collector"))
      (node (ref "SPI0-1/GPIO1") (pin "4") (pinfunction "4:MISO_4") (pintype "open_collector"))
    )
    (net (code "12") (name "GPIO10{slash}SPI1_MOSI") (class "Default")
      (node (ref "J41") (pin "19") (pinfunction "MOSI_19") (pintype "bidirectional"))
      (node (ref "SPI0-0/GPIO") (pin "6") (pinfunction "6:MOSI_6") (pintype "open_collector"))
      (node (ref "SPI0-1/GPIO1") (pin "6") (pinfunction "6:MOSI_6") (pintype "open_collector"))
      (node (ref "SW-SEL1") (pin "4") (pinfunction "4_4") (pintype "passive"))
    )
    (net (code "13") (name "GPIO11{slash}SPI1_SCLK") (class "Default")
      (node (ref "J41") (pin "23") (pinfunction "SCLK_23") (pintype "bidirectional"))
      (node (ref "SPI0-0/GPIO") (pin "2") (pinfunction "2:SCK_2") (pintype "open_collector"))
      (node (ref "SPI0-1/GPIO1") (pin "2") (pinfunction "2:SCK_2") (pintype "open_collector"))
    )
    (net (code "14") (name "GPIO12{slash}LCD_BL_PWM") (class "Default")
      (node (ref "GPIO12,13PWM") (pin "5") (pinfunction "5:PIN-A_5") (pintype "bidirectional"))
      (node (ref "J41") (pin "32") (pinfunction "GPIO12_32") (pintype "bidirectional"))
    )
    (net (code "15") (name "GPIO13{slash}GPIO_PE6") (class "Default")
      (node (ref "GPIO12,13PWM") (pin "6") (pinfunction "6:PIN-B_6") (pintype "bidirectional"))
      (node (ref "J41") (pin "33") (pinfunction "GPIO13_33") (pintype "bidirectional"))
    )
    (net (code "16") (name "GPIO14{slash}TXD") (class "Default")
      (node (ref "J41") (pin "8") (pinfunction "TX_8") (pintype "bidirectional"))
      (node (ref "UART2") (pin "5") (pinfunction "5:TX_5") (pintype "output"))
    )
    (net (code "17") (name "GPIO15{slash}RXD") (class "Default")
      (node (ref "J41") (pin "10") (pinfunction "RX_10") (pintype "bidirectional"))
      (node (ref "UART2") (pin "6") (pinfunction "6:RX_6") (pintype "input"))
    )
    (net (code "18") (name "GPIO16{slash}UART2_CTS") (class "Default")
      (node (ref "J41") (pin "36") (pinfunction "GPIO16_36") (pintype "bidirectional"))
      (node (ref "UART2") (pin "2") (pinfunction "2:CTS_2") (pintype "bidirectional"))
    )
    (net (code "19") (name "GPIO17{slash}UART2_RTS") (class "Default")
      (node (ref "J41") (pin "11") (pinfunction "GPIO17_11") (pintype "bidirectional"))
      (node (ref "UART2") (pin "4") (pinfunction "4:RTS_4") (pintype "bidirectional"))
    )
    (net (code "20") (name "GPIO18{slash}I2S0_SCLK") (class "Default")
      (node (ref "I2S0(DAP4)") (pin "4") (pinfunction "4:I2S_SCLK_4") (pintype "open_collector"))
      (node (ref "I2S0(DAP4)1") (pin "4") (pinfunction "4:I2S_SCLK_4") (pintype "open_collector"))
      (node (ref "J41") (pin "12") (pinfunction "GPIO18_12") (pintype "bidirectional"))
    )
    (net (code "21") (name "GPIO19{slash}I2S0_FS") (class "Default")
      (node (ref "I2S0(DAP4)") (pin "2") (pinfunction "2:I2S_FS_2") (pintype "input"))
      (node (ref "I2S0(DAP4)1") (pin "2") (pinfunction "2:I2S_FS_2") (pintype "input"))
      (node (ref "J41") (pin "35") (pinfunction "GPIO19_35") (pintype "bidirectional"))
    )
    (net (code "22") (name "GPIO20{slash}I2S0_DIN") (class "Default")
      (node (ref "I2S0(DAP4)1") (pin "5") (pinfunction "5:I2S_DIN_5") (pintype "input"))
      (node (ref "J41") (pin "38") (pinfunction "GPIO20_38") (pintype "bidirectional"))
    )
    (net (code "23") (name "GPIO21{slash}I2S0_DOUT") (class "Default")
      (node (ref "I2S0(DAP4)") (pin "6") (pinfunction "6:I2S_OUT_6") (pintype "output"))
      (node (ref "J41") (pin "40") (pinfunction "GPIO21_40") (pintype "bidirectional"))
    )
    (net (code "24") (name "GPIO22{slash}LCD_TE") (class "Default")
      (node (ref "GPIO5,6,22") (pin "4") (pinfunction "4:PIN-C_4") (pintype "bidirectional"))
      (node (ref "J41") (pin "15") (pinfunction "GPIO22_15") (pintype "bidirectional"))
    )
    (net (code "25") (name "GPIO23{slash}SPI2_CS1") (class "Default")
      (node (ref "J41") (pin "16") (pinfunction "GPIO23_16") (pintype "bidirectional"))
    )
    (net (code "26") (name "GPIO24{slash}SPI2_CS0") (class "Default")
      (node (ref "J41") (pin "18") (pinfunction "GPIO24_18") (pintype "bidirectional"))
      (node (ref "SPI2-0") (pin "5") (pinfunction "5:CS_5") (pintype "open_collector"))
    )
    (net (code "27") (name "GPIO25{slash}SPI2_MISO") (class "Default")
      (node (ref "J41") (pin "22") (pinfunction "GPIO25_22") (pintype "bidirectional"))
      (node (ref "SPI2-0") (pin "4") (pinfunction "4:MISO_4") (pintype "open_collector"))
    )
    (net (code "28") (name "GPIO26{slash}SPI2_MOSI") (class "Default")
      (node (ref "J41") (pin "37") (pinfunction "GPIO26_37") (pintype "bidirectional"))
      (node (ref "SPI2-0") (pin "6") (pinfunction "6:MOSI_6") (pintype "open_collector"))
    )
    (net (code "29") (name "GPIO27{slash}SPI2_SCK") (class "Default")
      (node (ref "J41") (pin "13") (pinfunction "GPIO27_13") (pintype "bidirectional"))
      (node (ref "SPI2-0") (pin "2") (pinfunction "2:SCK_2") (pintype "open_collector"))
    )
    (net (code "30") (name "I2C0_SCL") (class "Default")
      (node (ref "J41") (pin "28") (pinfunction "ID_SC_28") (pintype "bidirectional"))
    )
    (net (code "31") (name "I2C0_SDA") (class "Default")
      (node (ref "J41") (pin "27") (pinfunction "ID_SD_27") (pintype "bidirectional"))
    )
    (net (code "32") (name "NC1") (class "Default")
      (node (ref "J41") (pin "4") (pinfunction "5V_4") (pintype "bidirectional"))
    )
    (net (code "33") (name "NC2") (class "Default")
      (node (ref "J41") (pin "6") (pinfunction "GND_6") (pintype "bidirectional"))
    )
    (net (code "34") (name "Net-(GPIO4-3:VCC)") (class "Default")
      (node (ref "GPIO4") (pin "3") (pinfunction "3:VCC_3") (pintype "power_in"))
      (node (ref "U$32") (pin "2") (pinfunction "2_2") (pintype "bidirectional"))
    )
    (net (code "35") (name "Net-(GPIO4-5:PIN-A)") (class "Default")
      (node (ref "GPIO4") (pin "5") (pinfunction "5:PIN-A_5") (pintype "bidirectional"))
      (node (ref "SW-SEL1") (pin "5") (pinfunction "5_5") (pintype "passive"))
    )
    (net (code "36") (name "Net-(GPIO4-6:PIN-B)") (class "Default")
      (node (ref "GPIO4") (pin "6") (pinfunction "6:PIN-B_6") (pintype "bidirectional"))
      (node (ref "SW-SEL1") (pin "2") (pinfunction "2_2") (pintype "passive"))
    )
    (net (code "37") (name "Net-(GPIO5,6,22-3:VCC)") (class "Default")
      (node (ref "GPIO5,6,22") (pin "3") (pinfunction "3:VCC_3") (pintype "power_in"))
      (node (ref "U$3") (pin "2") (pinfunction "2_2") (pintype "bidirectional"))
    )
    (net (code "38") (name "unconnected-(GPIO4-2:NC-Pad2)") (class "Default")
      (node (ref "GPIO4") (pin "2") (pinfunction "2:NC_2") (pintype "no_connect"))
    )
    (net (code "39") (name "unconnected-(GPIO4-4:NC-Pad4)") (class "Default")
      (node (ref "GPIO4") (pin "4") (pinfunction "4:NC_4") (pintype "no_connect"))
    )
    (net (code "40") (name "unconnected-(GPIO5,6,22-2:NC-Pad2)") (class "Default")
      (node (ref "GPIO5,6,22") (pin "2") (pinfunction "2:NC_2") (pintype "no_connect"))
    )
    (net (code "41") (name "unconnected-(GPIO12,13PWM-2:NC-Pad2)") (class "Default")
      (node (ref "GPIO12,13PWM") (pin "2") (pinfunction "2:NC_2") (pintype "no_connect"))
    )
    (net (code "42") (name "unconnected-(GPIO12,13PWM-4:PIN-C-Pad4)") (class "Default")
      (node (ref "GPIO12,13PWM") (pin "4") (pinfunction "4:PIN-C_4") (pintype "bidirectional"))
    )
    (net (code "43") (name "unconnected-(I2C-2:NC-Pad2)") (class "Default")
      (node (ref "I2C") (pin "2") (pinfunction "2:NC_2") (pintype "no_connect"))
    )
    (net (code "44") (name "unconnected-(I2C-6:NC-Pad6)") (class "Default")
      (node (ref "I2C") (pin "6") (pinfunction "6:NC_6") (pintype "no_connect"))
    )
    (net (code "45") (name "unconnected-(I2C1-2:NC-Pad2)") (class "Default")
      (node (ref "I2C1") (pin "2") (pinfunction "2:NC_2") (pintype "no_connect"))
    )
    (net (code "46") (name "unconnected-(I2C1-6:NC-Pad6)") (class "Default")
      (node (ref "I2C1") (pin "6") (pinfunction "6:NC_6") (pintype "no_connect"))
    )
    (net (code "47") (name "unconnected-(I2S0(DAP4)-5:I2S_DIN-Pad5)") (class "Default")
      (node (ref "I2S0(DAP4)") (pin "5") (pinfunction "5:I2S_DIN_5") (pintype "input"))
    )
    (net (code "48") (name "unconnected-(I2S0(DAP4)1-6:I2S_OUT-Pad6)") (class "Default")
      (node (ref "I2S0(DAP4)1") (pin "6") (pinfunction "6:I2S_OUT_6") (pintype "output"))
    )
    (net (code "49") (name "unconnected-(SW-SEL1-Pad1)") (class "Default")
      (node (ref "SW-SEL1") (pin "1") (pinfunction "1_1") (pintype "passive"))
    )
    (net (code "50") (name "unconnected-(SW-SEL1-Pad3)") (class "Default")
      (node (ref "SW-SEL1") (pin "3") (pinfunction "3_3") (pintype "passive"))
    )
  )
)
